# BlueBoard_v1.net
KiCad netlist of a schematic drawn in EAGLE
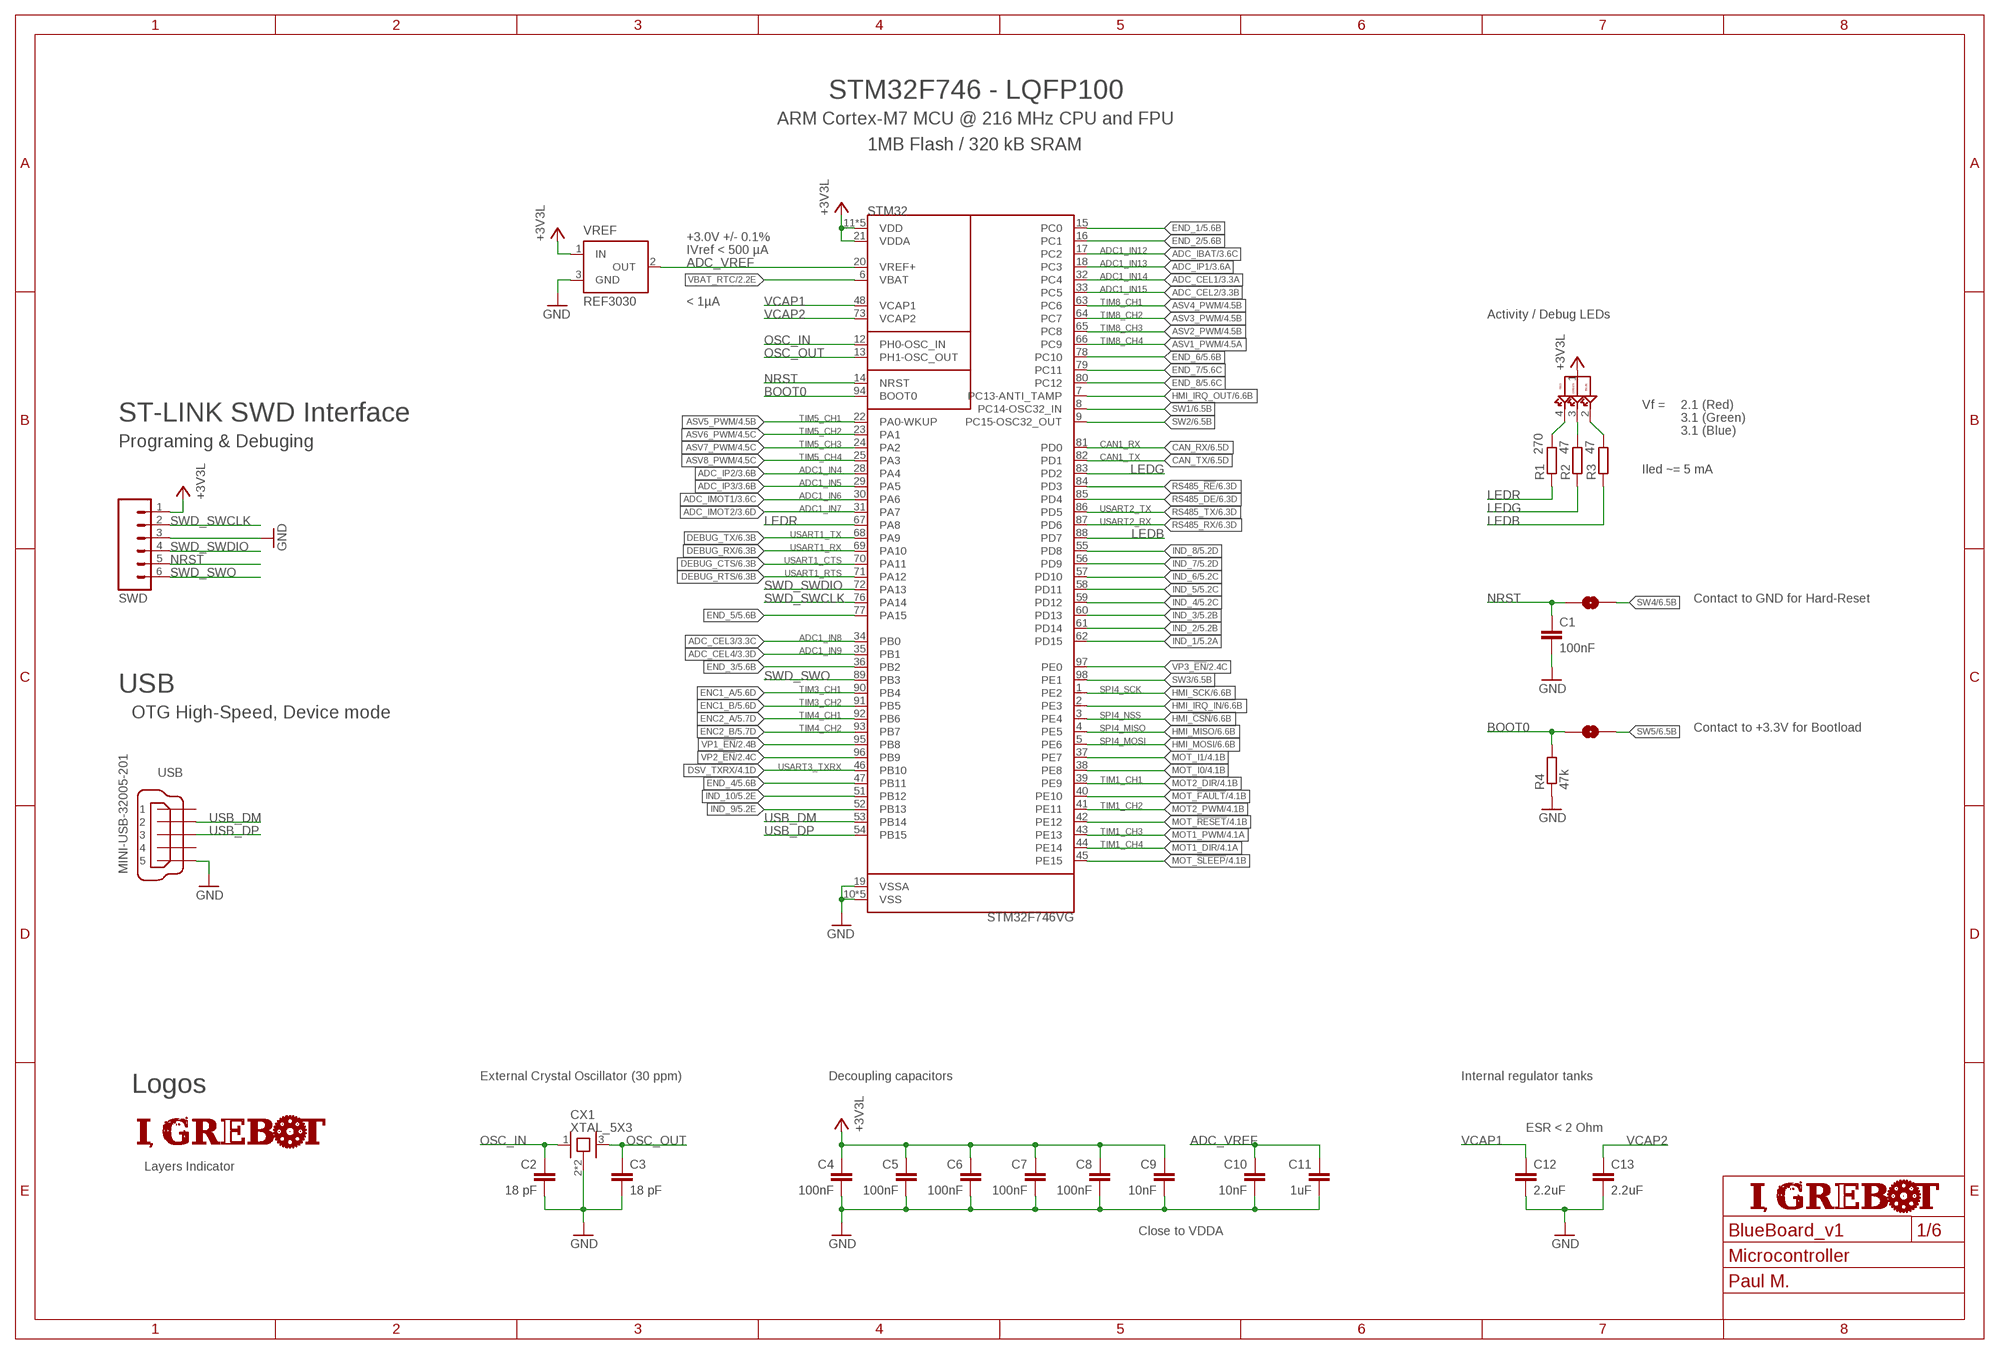
[diagram p0: schematic, sheet 1]
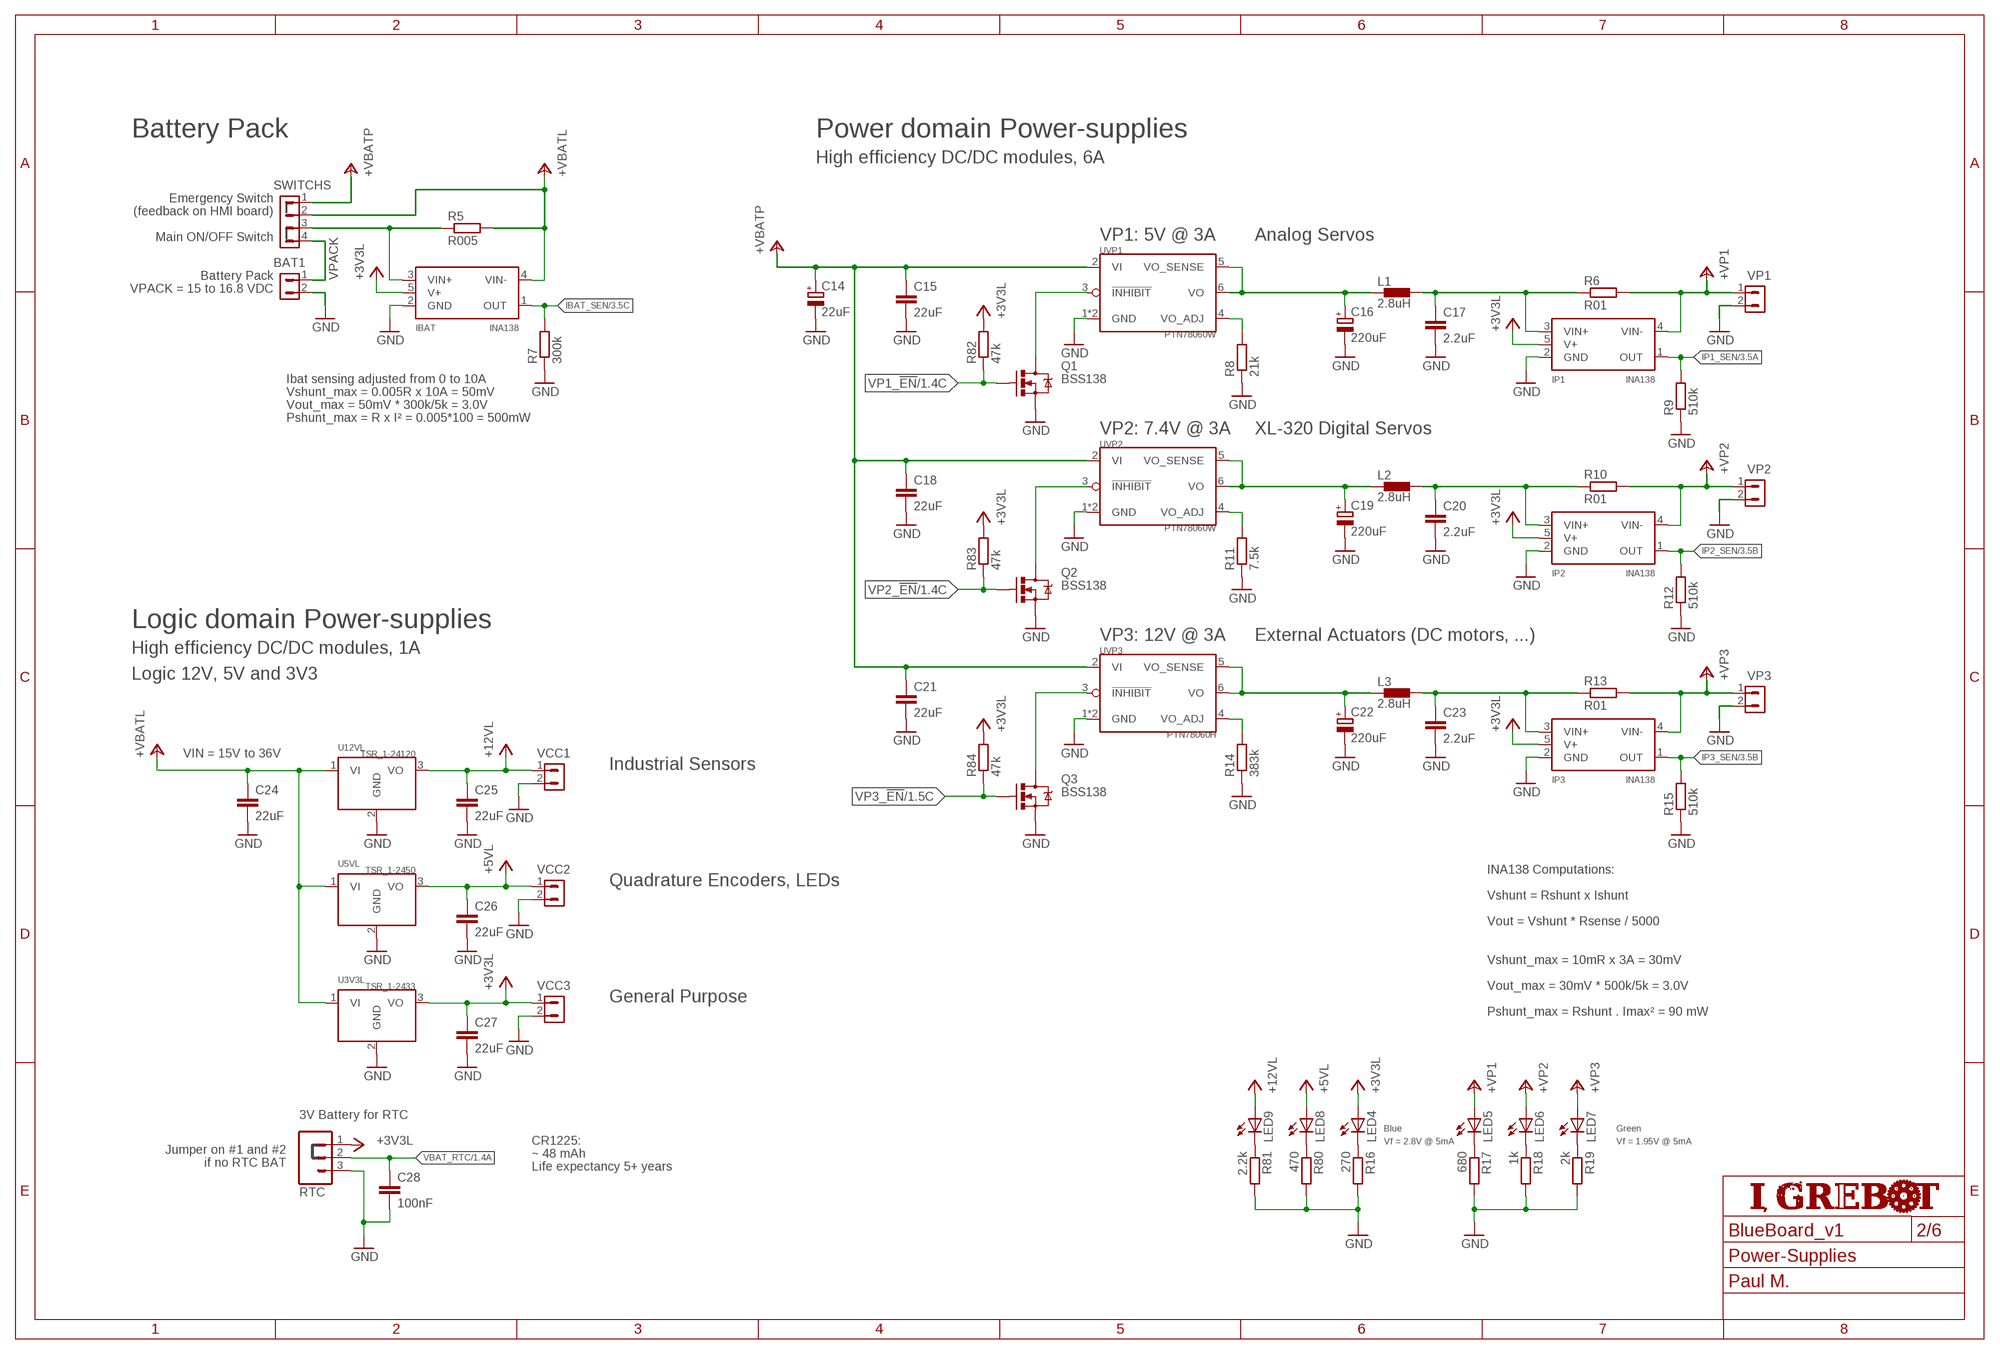
[diagram p1: schematic, sheet 2]
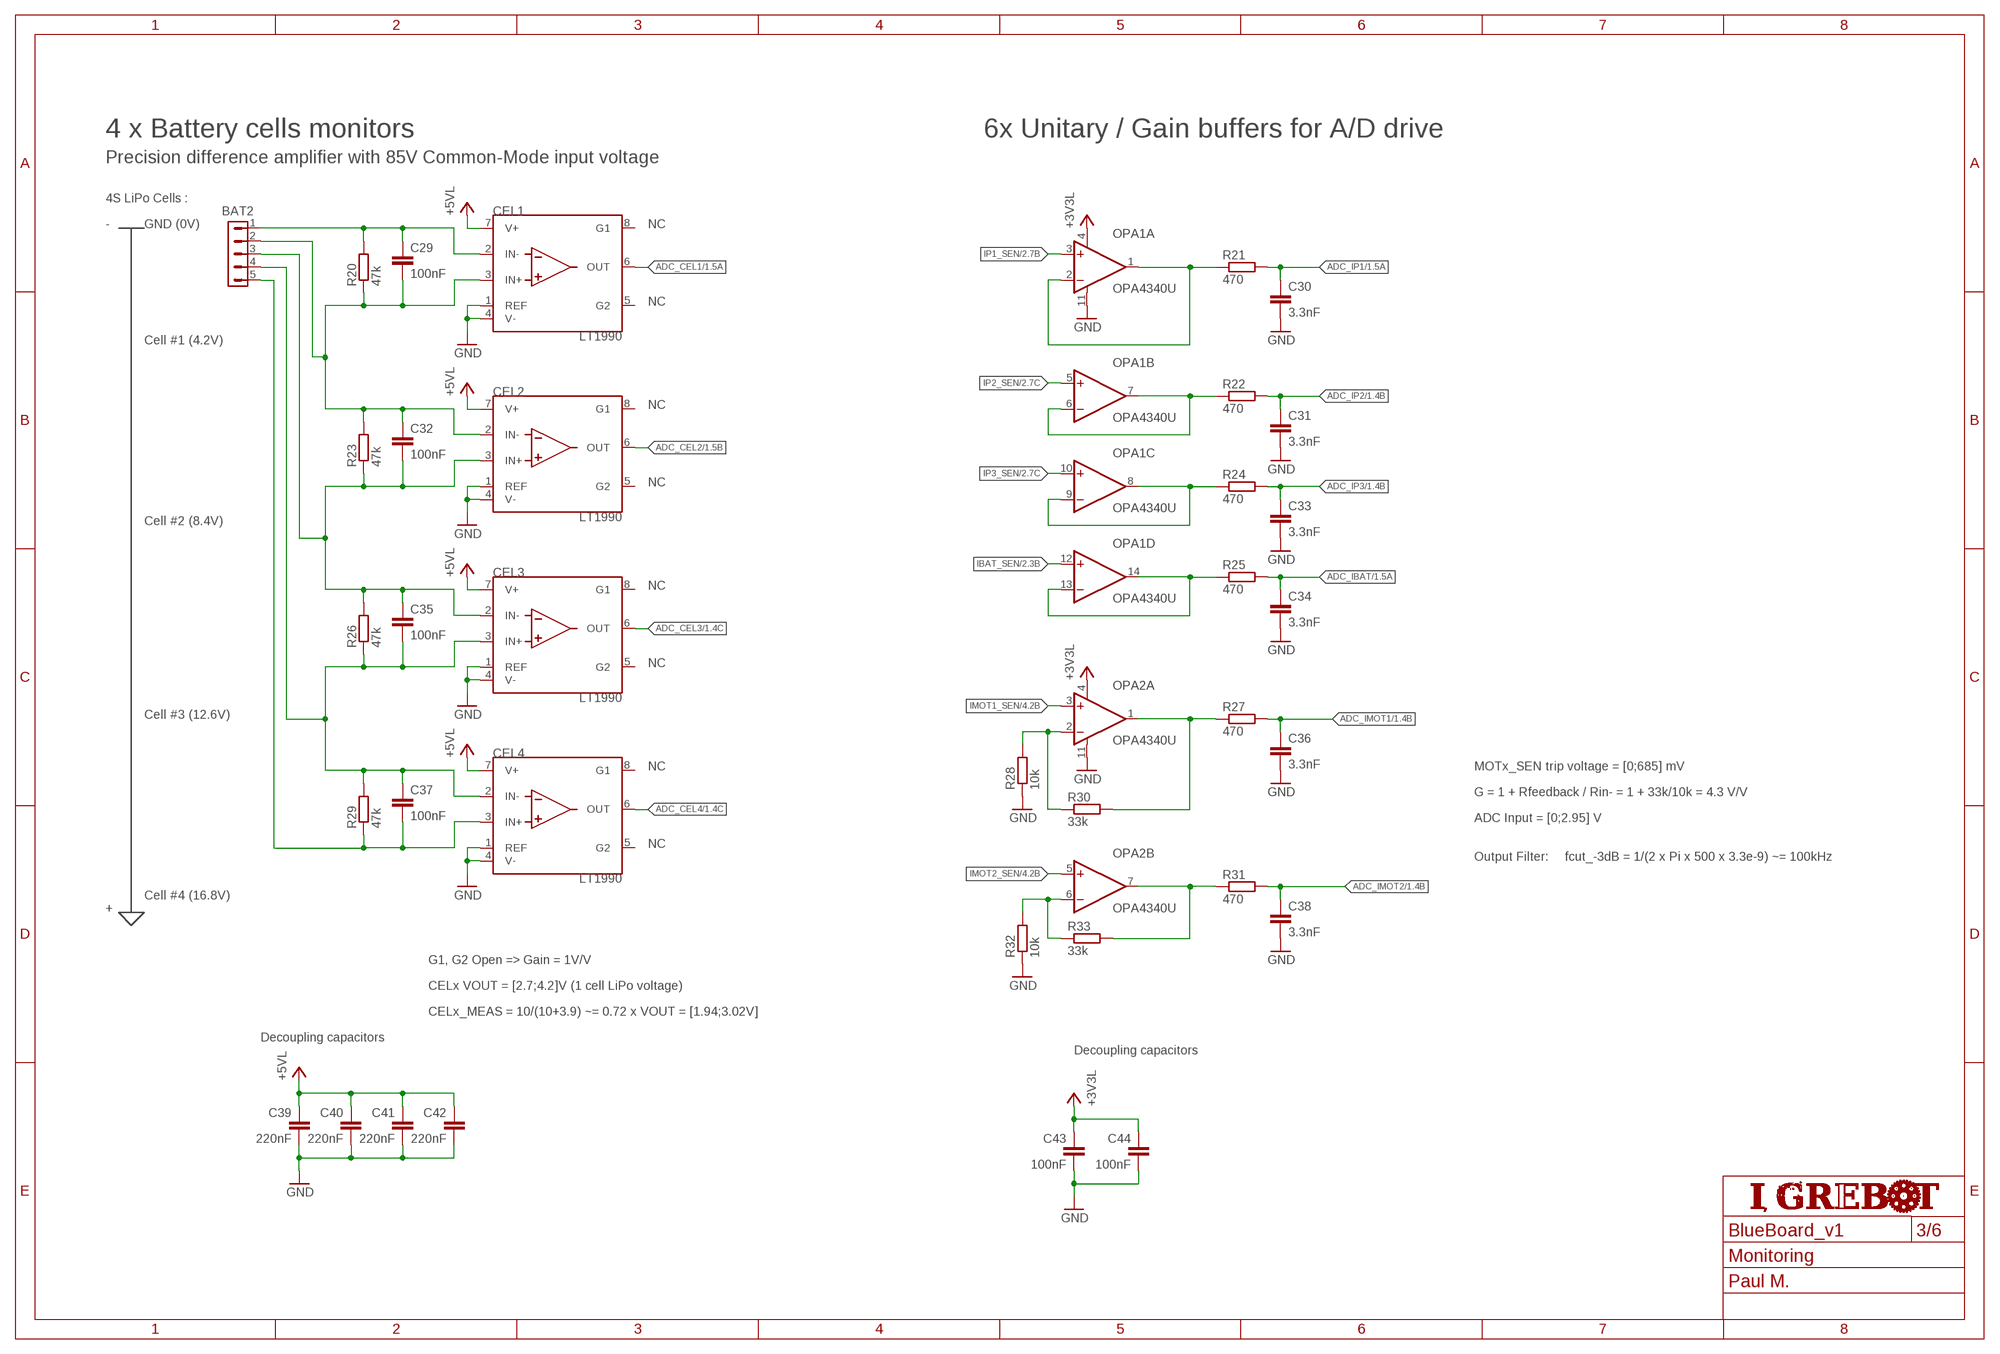
[diagram p2: schematic, sheet 3]
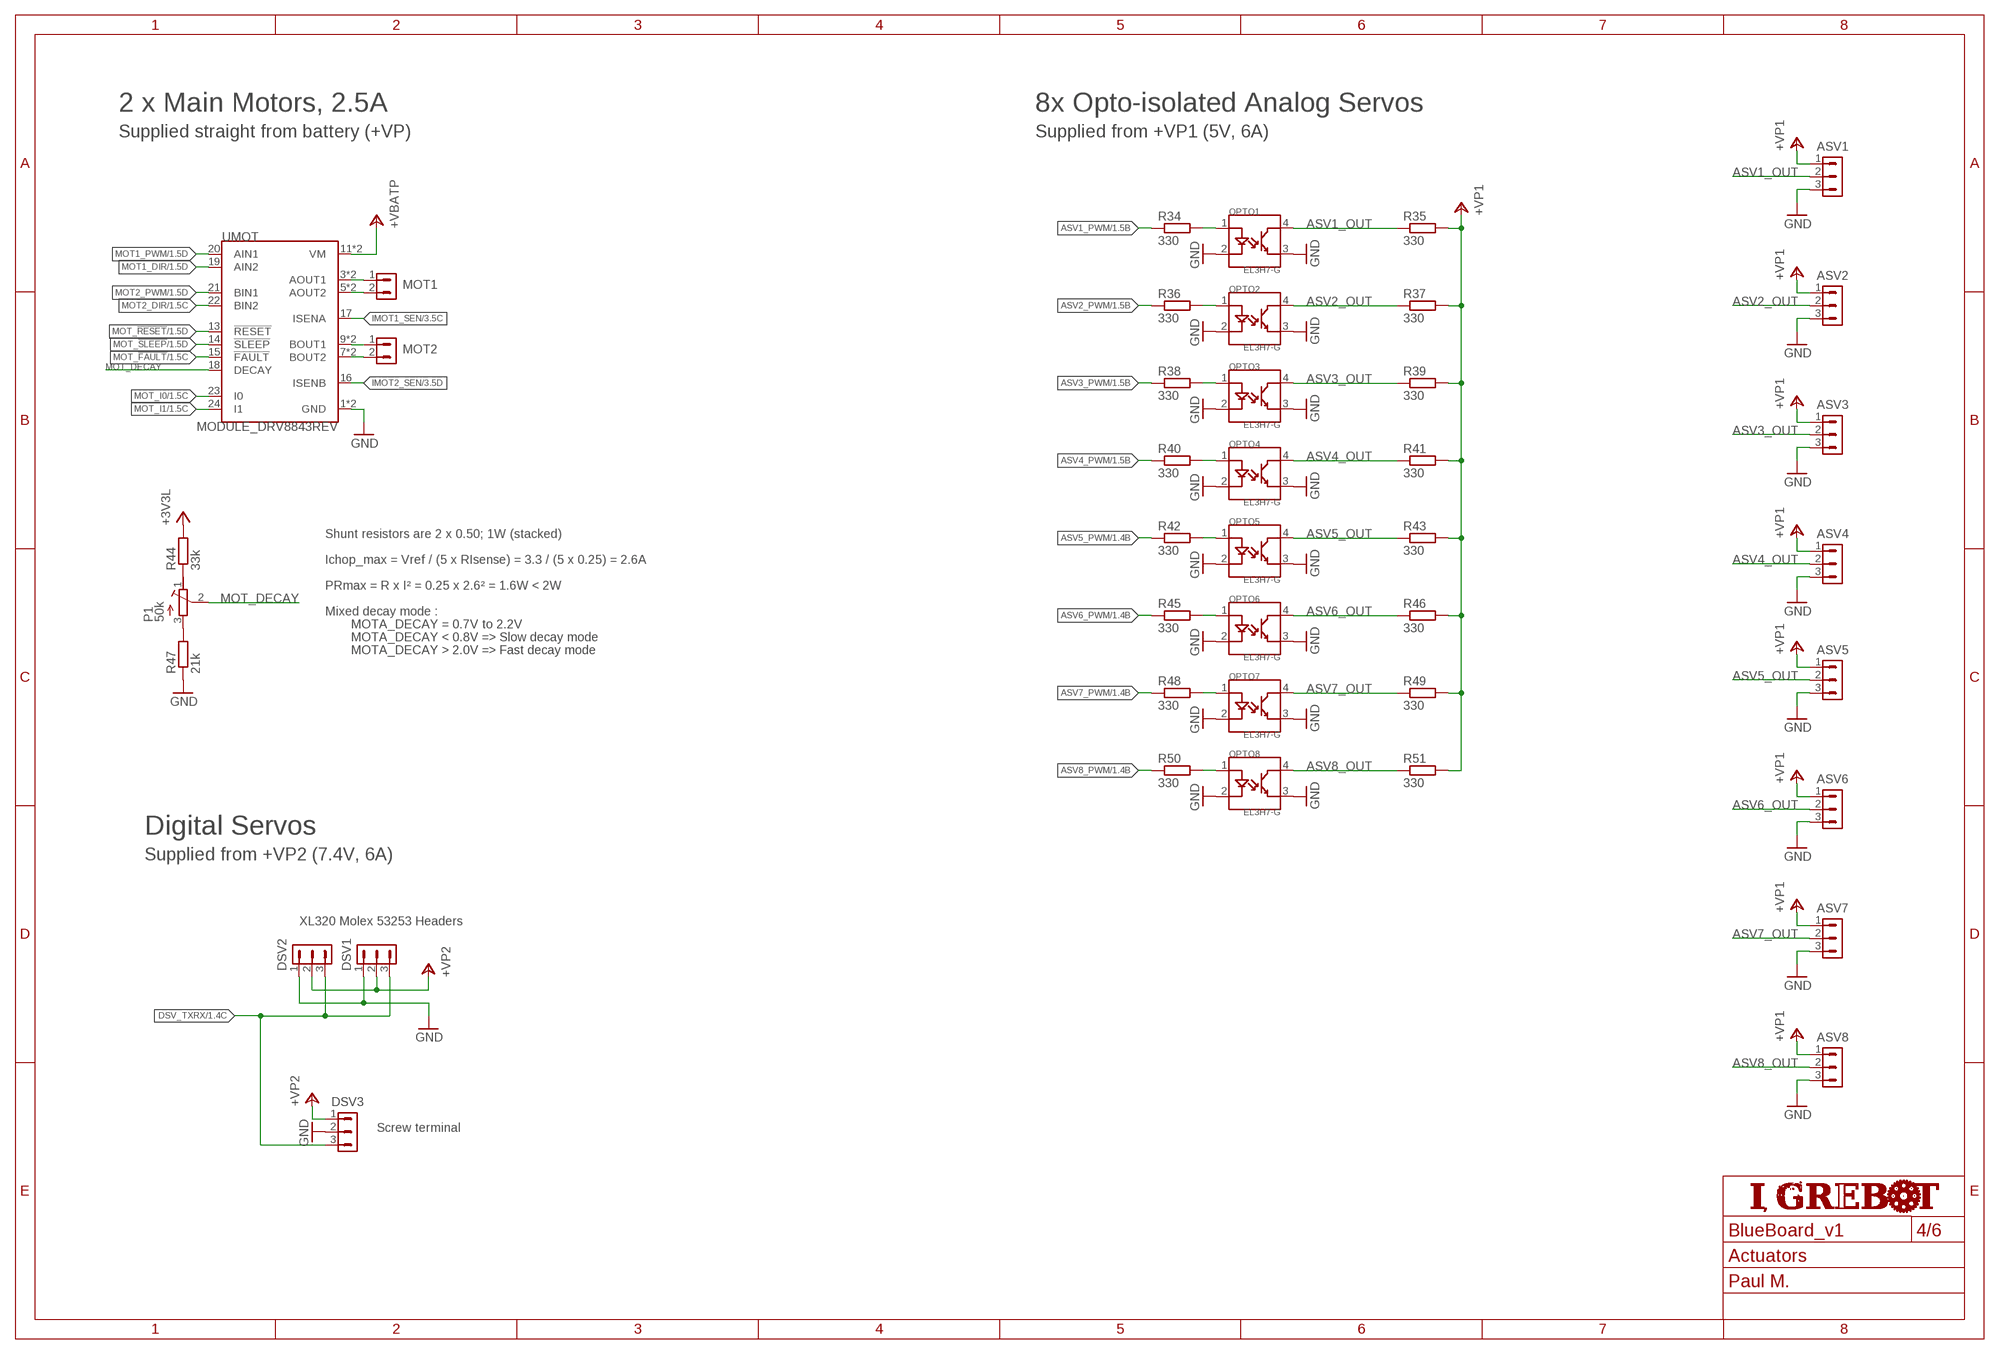
[diagram p3: schematic, sheet 4]
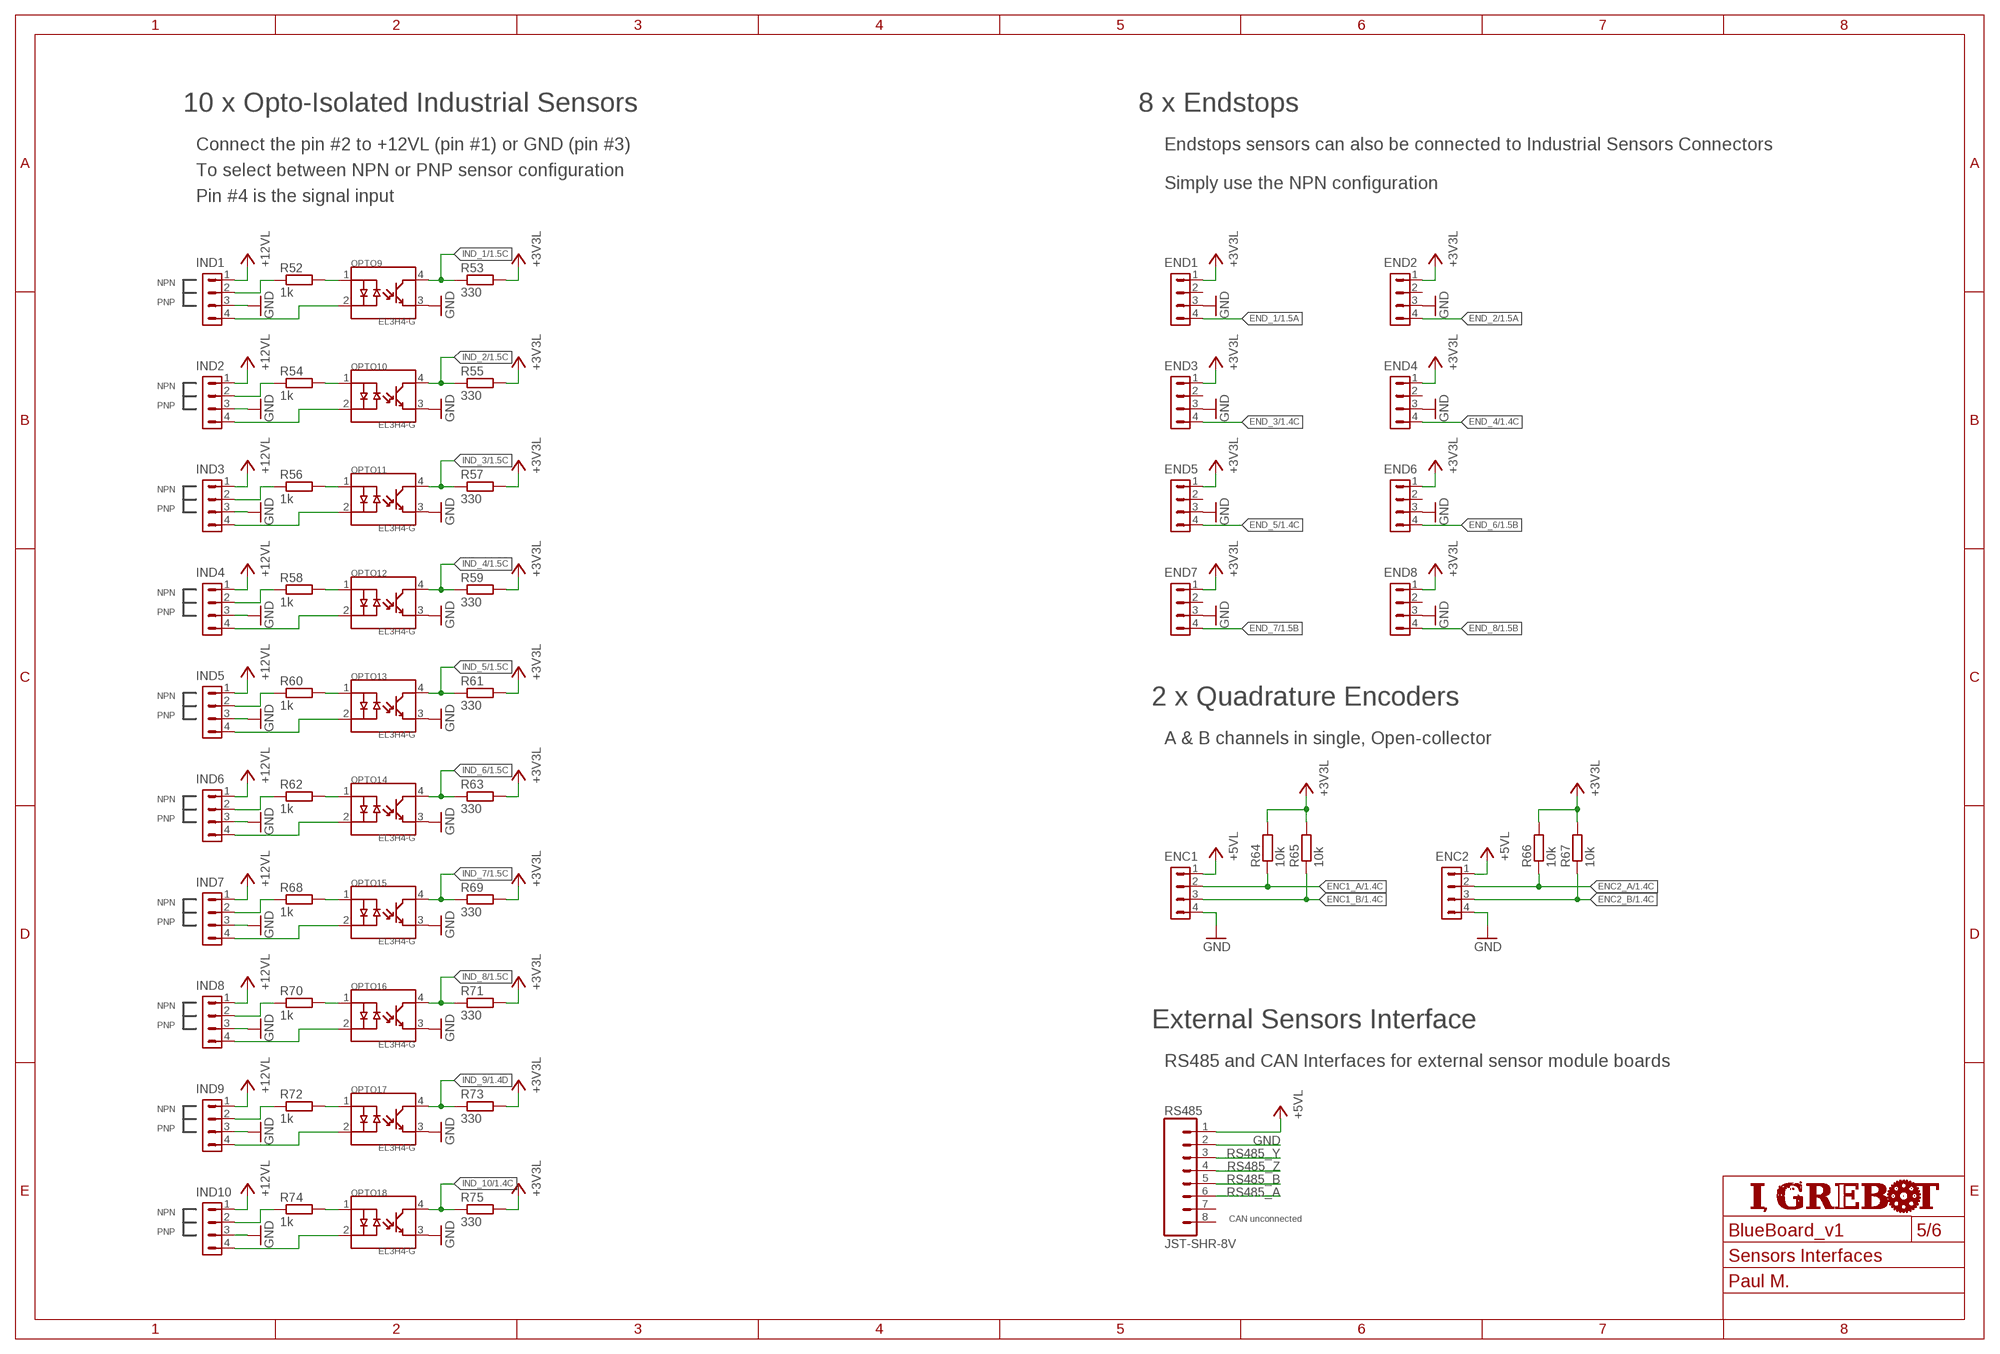
[diagram p4: schematic, sheet 5]
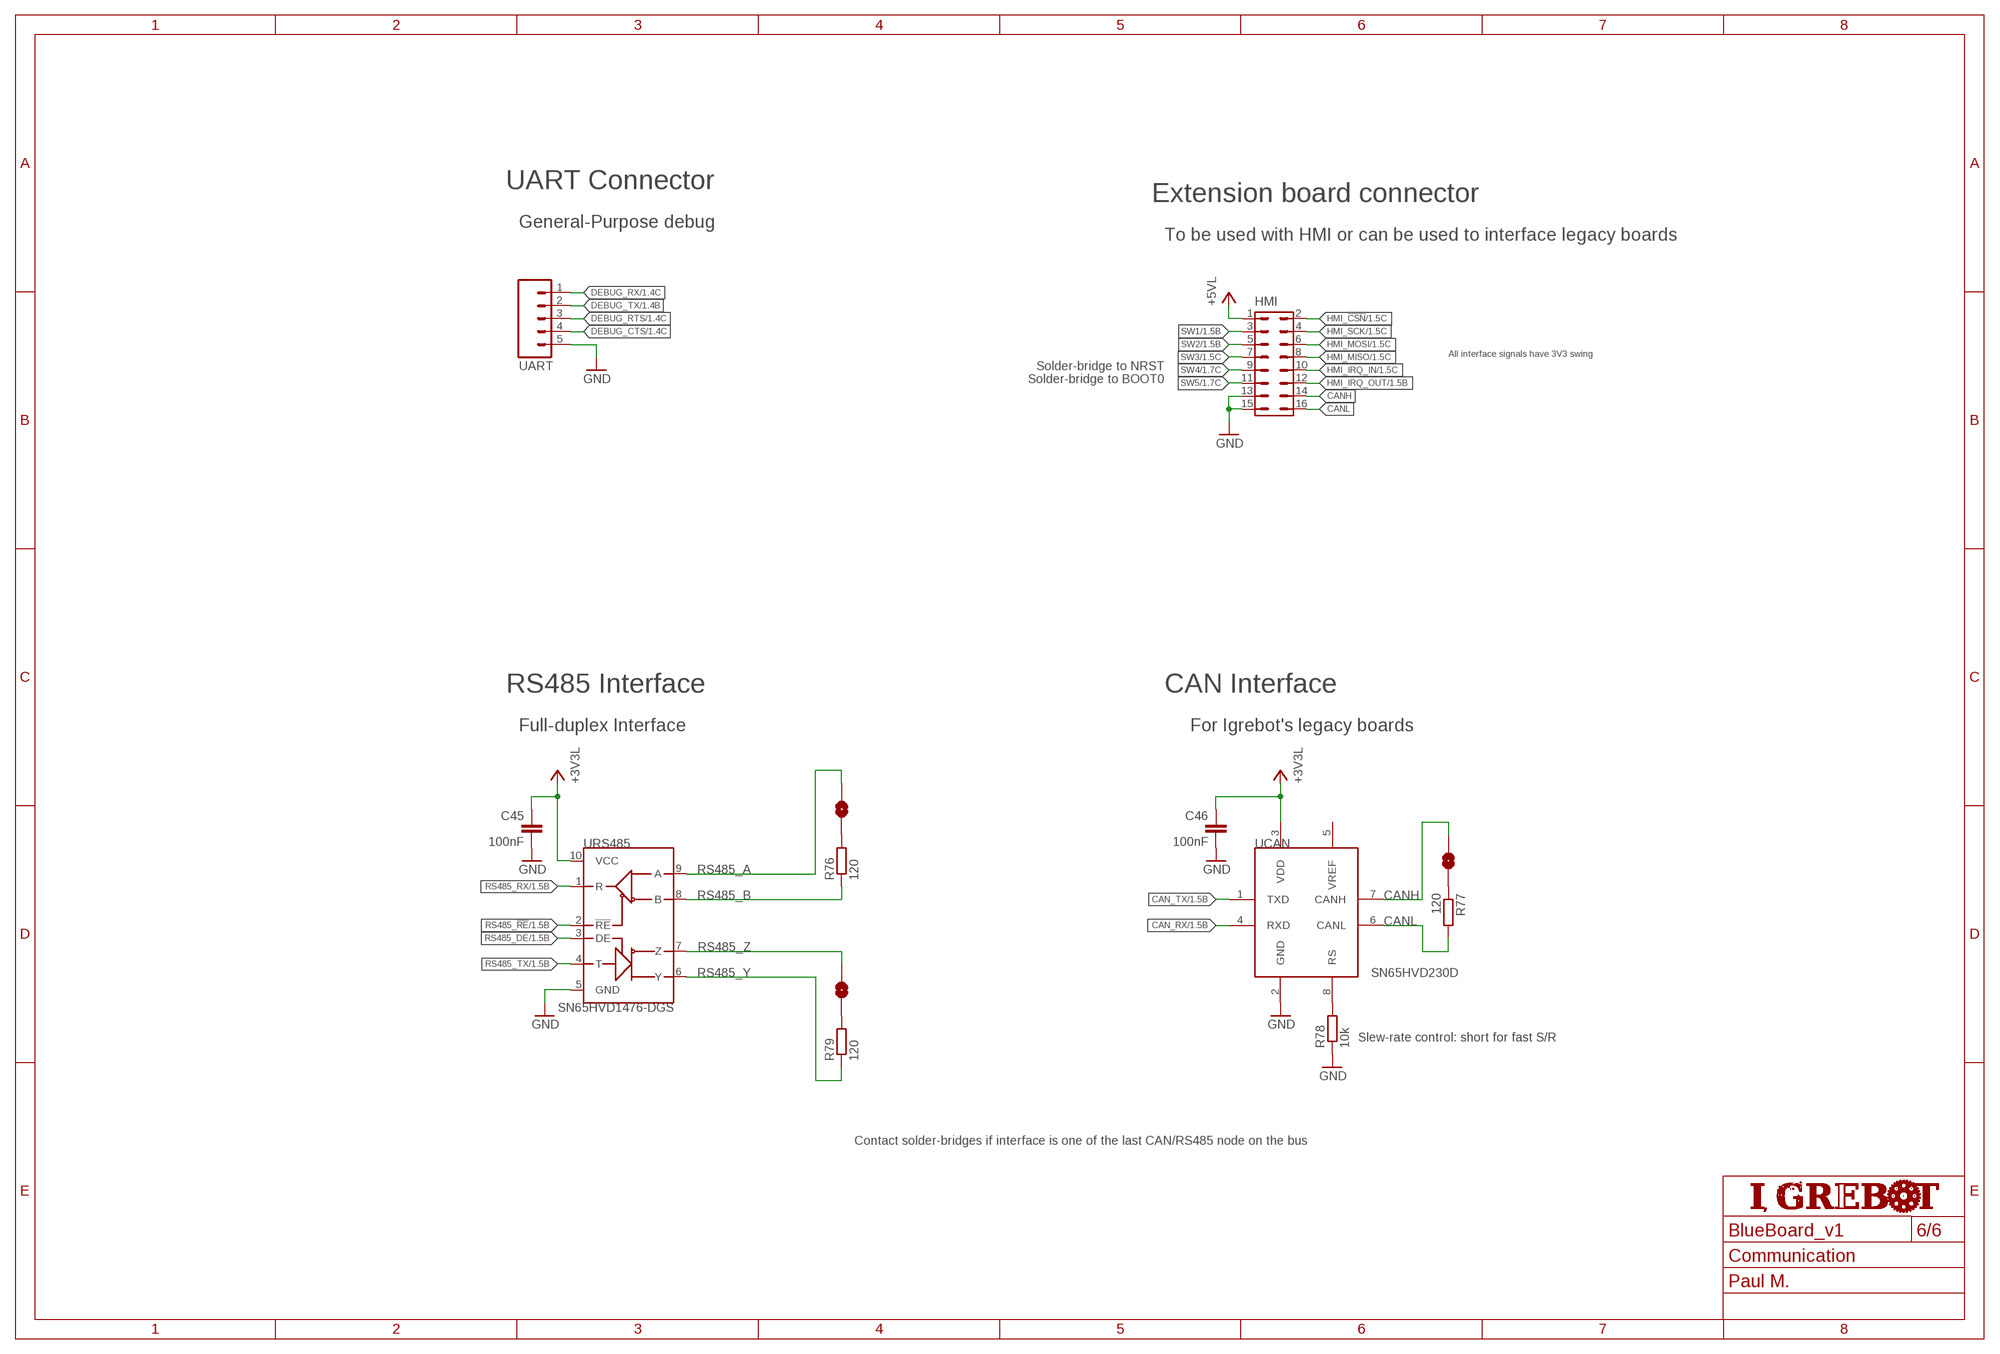
[diagram p5: schematic, sheet 6]

(export (version "E")
  (design (tool "Eeschema 10.0.6"))
  (components
    (comp (ref "BAT2")
      (value "JST-XH-S_5")
      (footprint "eagle-import:JST-XH-5S")
      (libsource (lib "eagle-import") (part "JST-XH-S_5"))
    )
    (comp (ref "C29")
      (value "100nF")
      (footprint "eagle-import:C0603")
      (libsource (lib "eagle-import") (part "C-EUC0603"))
    )
    (comp (ref "C30")
      (value "3.3nF")
      (footprint "eagle-import:C0603")
      (libsource (lib "eagle-import") (part "C-EUC0603"))
    )
    (comp (ref "C31")
      (value "3.3nF")
      (footprint "eagle-import:C0603")
      (libsource (lib "eagle-import") (part "C-EUC0603"))
    )
    (comp (ref "C32")
      (value "100nF")
      (footprint "eagle-import:C0603")
      (libsource (lib "eagle-import") (part "C-EUC0603"))
    )
    (comp (ref "C33")
      (value "3.3nF")
      (footprint "eagle-import:C0603")
      (libsource (lib "eagle-import") (part "C-EUC0603"))
    )
    (comp (ref "C34")
      (value "3.3nF")
      (footprint "eagle-import:C0603")
      (libsource (lib "eagle-import") (part "C-EUC0603"))
    )
    (comp (ref "C35")
      (value "100nF")
      (footprint "eagle-import:C0603")
      (libsource (lib "eagle-import") (part "C-EUC0603"))
    )
    (comp (ref "C36")
      (value "3.3nF")
      (footprint "eagle-import:C0603")
      (libsource (lib "eagle-import") (part "C-EUC0603"))
    )
    (comp (ref "C37")
      (value "100nF")
      (footprint "eagle-import:C0603")
      (libsource (lib "eagle-import") (part "C-EUC0603"))
    )
    (comp (ref "C38")
      (value "3.3nF")
      (footprint "eagle-import:C0603")
      (libsource (lib "eagle-import") (part "C-EUC0603"))
    )
    (comp (ref "C39")
      (value "220nF")
      (footprint "eagle-import:C0603")
      (libsource (lib "eagle-import") (part "C-EUC0603"))
    )
    (comp (ref "C40")
      (value "220nF")
      (footprint "eagle-import:C0603")
      (libsource (lib "eagle-import") (part "C-EUC0603"))
    )
    (comp (ref "C41")
      (value "220nF")
      (footprint "eagle-import:C0603")
      (libsource (lib "eagle-import") (part "C-EUC0603"))
    )
    (comp (ref "C42")
      (value "220nF")
      (footprint "eagle-import:C0603")
      (libsource (lib "eagle-import") (part "C-EUC0603"))
    )
    (comp (ref "C43")
      (value "100nF")
      (footprint "eagle-import:C0603")
      (libsource (lib "eagle-import") (part "C-EUC0603"))
    )
    (comp (ref "C44")
      (value "100nF")
      (footprint "eagle-import:C0603")
      (libsource (lib "eagle-import") (part "C-EUC0603"))
    )
    (comp (ref "CEL1")
      (value "LT1990")
      (footprint "eagle-import:S8")
      (libsource (lib "eagle-import") (part "LT1990"))
    )
    (comp (ref "CEL2")
      (value "LT1990")
      (footprint "eagle-import:S8")
      (libsource (lib "eagle-import") (part "LT1990"))
    )
    (comp (ref "CEL3")
      (value "LT1990")
      (footprint "eagle-import:S8")
      (libsource (lib "eagle-import") (part "LT1990"))
    )
    (comp (ref "CEL4")
      (value "LT1990")
      (footprint "eagle-import:S8")
      (libsource (lib "eagle-import") (part "LT1990"))
    )
    (comp (ref "OPA1")
      (value "OPA4340U")
      (footprint "eagle-import:SO14")
      (fields (field (name "MF") "TEXAS INSTRUMENTS") (field (name "MPN") "OPA4340UA"))
      (libsource (lib "eagle-import") (part "OPA4340U"))
    )
    (comp (ref "OPA2")
      (value "OPA4340U")
      (footprint "eagle-import:SO14")
      (fields (field (name "MF") "TEXAS INSTRUMENTS") (field (name "MPN") "OPA4340UA"))
      (libsource (lib "eagle-import") (part "OPA4340U"))
    )
    (comp (ref "R20")
      (value "47k")
      (footprint "eagle-import:R0603")
      (libsource (lib "eagle-import") (part "resistor_R-EU_R0603"))
    )
    (comp (ref "R21")
      (value "470")
      (footprint "eagle-import:R0603")
      (libsource (lib "eagle-import") (part "R-EU_R0603"))
    )
    (comp (ref "R22")
      (value "470")
      (footprint "eagle-import:R0603")
      (libsource (lib "eagle-import") (part "R-EU_R0603"))
    )
    (comp (ref "R23")
      (value "47k")
      (footprint "eagle-import:R0603")
      (libsource (lib "eagle-import") (part "resistor_R-EU_R0603"))
    )
    (comp (ref "R24")
      (value "470")
      (footprint "eagle-import:R0603")
      (libsource (lib "eagle-import") (part "R-EU_R0603"))
    )
    (comp (ref "R25")
      (value "470")
      (footprint "eagle-import:R0603")
      (libsource (lib "eagle-import") (part "R-EU_R0603"))
    )
    (comp (ref "R26")
      (value "47k")
      (footprint "eagle-import:R0603")
      (libsource (lib "eagle-import") (part "resistor_R-EU_R0603"))
    )
    (comp (ref "R27")
      (value "470")
      (footprint "eagle-import:R0603")
      (libsource (lib "eagle-import") (part "R-EU_R0603"))
    )
    (comp (ref "R28")
      (value "10k")
      (footprint "eagle-import:R0603")
      (libsource (lib "eagle-import") (part "R-EU_R0603"))
    )
    (comp (ref "R29")
      (value "47k")
      (footprint "eagle-import:R0603")
      (libsource (lib "eagle-import") (part "resistor_R-EU_R0603"))
    )
    (comp (ref "R30")
      (value "33k")
      (footprint "eagle-import:R0603")
      (libsource (lib "eagle-import") (part "R-EU_R0603"))
    )
    (comp (ref "R31")
      (value "470")
      (footprint "eagle-import:R0603")
      (libsource (lib "eagle-import") (part "R-EU_R0603"))
    )
    (comp (ref "R32")
      (value "10k")
      (footprint "eagle-import:R0603")
      (libsource (lib "eagle-import") (part "R-EU_R0603"))
    )
    (comp (ref "R33")
      (value "33k")
      (footprint "eagle-import:R0603")
      (libsource (lib "eagle-import") (part "R-EU_R0603"))
    )
    (comp (ref "ASV1")
      (value "CON_3.5_3")
      (footprint "eagle-import:CON_3.5_3")
      (libsource (lib "eagle-import") (part "CON_3.5_3"))
    )
    (comp (ref "ASV2")
      (value "CON_3.5_3")
      (footprint "eagle-import:CON_3.5_3")
      (libsource (lib "eagle-import") (part "CON_3.5_3"))
    )
    (comp (ref "ASV3")
      (value "CON_3.5_3")
      (footprint "eagle-import:CON_3.5_3")
      (libsource (lib "eagle-import") (part "CON_3.5_3"))
    )
    (comp (ref "ASV4")
      (value "CON_3.5_3")
      (footprint "eagle-import:CON_3.5_3")
      (libsource (lib "eagle-import") (part "CON_3.5_3"))
    )
    (comp (ref "ASV5")
      (value "CON_3.5_3")
      (footprint "eagle-import:CON_3.5_3")
      (libsource (lib "eagle-import") (part "CON_3.5_3"))
    )
    (comp (ref "ASV6")
      (value "CON_3.5_3")
      (footprint "eagle-import:CON_3.5_3")
      (libsource (lib "eagle-import") (part "CON_3.5_3"))
    )
    (comp (ref "ASV7")
      (value "CON_3.5_3")
      (footprint "eagle-import:CON_3.5_3")
      (libsource (lib "eagle-import") (part "CON_3.5_3"))
    )
    (comp (ref "ASV8")
      (value "CON_3.5_3")
      (footprint "eagle-import:CON_3.5_3")
      (libsource (lib "eagle-import") (part "CON_3.5_3"))
    )
    (comp (ref "DSV1")
      (value "CON_2.00_MOLEX-53253_3")
      (footprint "eagle-import:CON_2.00_MOLEX-53253_3")
      (libsource (lib "eagle-import") (part "CON_2.00_MOLEX-53253_3"))
    )
    (comp (ref "DSV2")
      (value "CON_2.00_MOLEX-53253_3")
      (footprint "eagle-import:CON_2.00_MOLEX-53253_3")
      (libsource (lib "eagle-import") (part "CON_2.00_MOLEX-53253_3"))
    )
    (comp (ref "DSV3")
      (value "CON_3.5_3")
      (footprint "eagle-import:CON_3.5_3")
      (libsource (lib "eagle-import") (part "CON_3.5_3"))
    )
    (comp (ref "MOT1")
      (value "CON_3.5_2")
      (footprint "eagle-import:CON_3.5_2")
      (libsource (lib "eagle-import") (part "CON_3.5_2"))
    )
    (comp (ref "MOT2")
      (value "CON_3.5_2")
      (footprint "eagle-import:CON_3.5_2")
      (libsource (lib "eagle-import") (part "CON_3.5_2"))
    )
    (comp (ref "OPTO1")
      (value "EL3H7-G")
      (footprint "eagle-import:SSOP_4")
      (libsource (lib "eagle-import") (part "EL3H7-G"))
    )
    (comp (ref "OPTO2")
      (value "EL3H7-G")
      (footprint "eagle-import:SSOP_4")
      (libsource (lib "eagle-import") (part "EL3H7-G"))
    )
    (comp (ref "OPTO3")
      (value "EL3H7-G")
      (footprint "eagle-import:SSOP_4")
      (libsource (lib "eagle-import") (part "EL3H7-G"))
    )
    (comp (ref "OPTO4")
      (value "EL3H7-G")
      (footprint "eagle-import:SSOP_4")
      (libsource (lib "eagle-import") (part "EL3H7-G"))
    )
    (comp (ref "OPTO5")
      (value "EL3H7-G")
      (footprint "eagle-import:SSOP_4")
      (libsource (lib "eagle-import") (part "EL3H7-G"))
    )
    (comp (ref "OPTO6")
      (value "EL3H7-G")
      (footprint "eagle-import:SSOP_4")
      (libsource (lib "eagle-import") (part "EL3H7-G"))
    )
    (comp (ref "OPTO7")
      (value "EL3H7-G")
      (footprint "eagle-import:SSOP_4")
      (libsource (lib "eagle-import") (part "EL3H7-G"))
    )
    (comp (ref "OPTO8")
      (value "EL3H7-G")
      (footprint "eagle-import:SSOP_4")
      (libsource (lib "eagle-import") (part "EL3H7-G"))
    )
    (comp (ref "P1")
      (value "50k")
      (footprint "eagle-import:RTRIMT93XB")
      (libsource (lib "eagle-import") (part "R-TRIMMT93XB"))
    )
    (comp (ref "R34")
      (value "330")
      (footprint "eagle-import:R0603")
      (libsource (lib "eagle-import") (part "resistor_R-EU_R0603"))
    )
    (comp (ref "R35")
      (value "330")
      (footprint "eagle-import:R0603")
      (libsource (lib "eagle-import") (part "resistor_R-EU_R0603"))
    )
    (comp (ref "R36")
      (value "330")
      (footprint "eagle-import:R0603")
      (libsource (lib "eagle-import") (part "resistor_R-EU_R0603"))
    )
    (comp (ref "R37")
      (value "330")
      (footprint "eagle-import:R0603")
      (libsource (lib "eagle-import") (part "resistor_R-EU_R0603"))
    )
    (comp (ref "R38")
      (value "330")
      (footprint "eagle-import:R0603")
      (libsource (lib "eagle-import") (part "resistor_R-EU_R0603"))
    )
    (comp (ref "R39")
      (value "330")
      (footprint "eagle-import:R0603")
      (libsource (lib "eagle-import") (part "resistor_R-EU_R0603"))
    )
    (comp (ref "R40")
      (value "330")
      (footprint "eagle-import:R0603")
      (libsource (lib "eagle-import") (part "resistor_R-EU_R0603"))
    )
    (comp (ref "R41")
      (value "330")
      (footprint "eagle-import:R0603")
      (libsource (lib "eagle-import") (part "resistor_R-EU_R0603"))
    )
    (comp (ref "R42")
      (value "330")
      (footprint "eagle-import:R0603")
      (libsource (lib "eagle-import") (part "resistor_R-EU_R0603"))
    )
    (comp (ref "R43")
      (value "330")
      (footprint "eagle-import:R0603")
      (libsource (lib "eagle-import") (part "resistor_R-EU_R0603"))
    )
    (comp (ref "R44")
      (value "33k")
      (footprint "eagle-import:R0603")
      (libsource (lib "eagle-import") (part "resistor_R-EU_R0603"))
    )
    (comp (ref "R45")
      (value "330")
      (footprint "eagle-import:R0603")
      (libsource (lib "eagle-import") (part "resistor_R-EU_R0603"))
    )
    (comp (ref "R46")
      (value "330")
      (footprint "eagle-import:R0603")
      (libsource (lib "eagle-import") (part "resistor_R-EU_R0603"))
    )
    (comp (ref "R47")
      (value "21k")
      (footprint "eagle-import:R0603")
      (libsource (lib "eagle-import") (part "resistor_R-EU_R0603"))
    )
    (comp (ref "R48")
      (value "330")
      (footprint "eagle-import:R0603")
      (libsource (lib "eagle-import") (part "resistor_R-EU_R0603"))
    )
    (comp (ref "R49")
      (value "330")
      (footprint "eagle-import:R0603")
      (libsource (lib "eagle-import") (part "resistor_R-EU_R0603"))
    )
    (comp (ref "R50")
      (value "330")
      (footprint "eagle-import:R0603")
      (libsource (lib "eagle-import") (part "resistor_R-EU_R0603"))
    )
    (comp (ref "R51")
      (value "330")
      (footprint "eagle-import:R0603")
      (libsource (lib "eagle-import") (part "resistor_R-EU_R0603"))
    )
    (comp (ref "UMOT")
      (value "MODULE_DRV8843REV")
      (footprint "eagle-import:MODULE_DRV884X_REV")
      (libsource (lib "eagle-import") (part "MODULE_DRV8843REV"))
    )
    (comp (ref "BAT1")
      (value "MC15-GF-3.81-LR_2")
      (footprint "eagle-import:CON_3.81_LR_2")
      (libsource (lib "eagle-import") (part "MC15-GF-3.81-LR_2"))
    )
    (comp (ref "C14")
      (value "22uF")
      (footprint "eagle-import:PANASONIC_B")
      (libsource (lib "eagle-import") (part "CPOL-EUB"))
    )
    (comp (ref "C15")
      (value "22uF")
      (footprint "eagle-import:C3225")
      (libsource (lib "eagle-import") (part "C-EUC3225"))
    )
    (comp (ref "C16")
      (value "220uF")
      (footprint "eagle-import:PANASONIC_D")
      (libsource (lib "eagle-import") (part "CPOL-EUD"))
    )
    (comp (ref "C17")
      (value "2.2uF")
      (footprint "eagle-import:C3225")
      (libsource (lib "eagle-import") (part "C-EUC3225"))
    )
    (comp (ref "C18")
      (value "22uF")
      (footprint "eagle-import:C3225")
      (libsource (lib "eagle-import") (part "C-EUC3225"))
    )
    (comp (ref "C19")
      (value "220uF")
      (footprint "eagle-import:PANASONIC_D")
      (libsource (lib "eagle-import") (part "CPOL-EUD"))
    )
    (comp (ref "C20")
      (value "2.2uF")
      (footprint "eagle-import:C3225")
      (libsource (lib "eagle-import") (part "C-EUC3225"))
    )
    (comp (ref "C21")
      (value "22uF")
      (footprint "eagle-import:C3225")
      (libsource (lib "eagle-import") (part "C-EUC3225"))
    )
    (comp (ref "C22")
      (value "220uF")
      (footprint "eagle-import:PANASONIC_D")
      (libsource (lib "eagle-import") (part "CPOL-EUD"))
    )
    (comp (ref "C23")
      (value "2.2uF")
      (footprint "eagle-import:C3225")
      (libsource (lib "eagle-import") (part "C-EUC3225"))
    )
    (comp (ref "C24")
      (value "22uF")
      (footprint "eagle-import:C3225")
      (libsource (lib "eagle-import") (part "C-EUC3225"))
    )
    (comp (ref "C25")
      (value "22uF")
      (footprint "eagle-import:C1210")
      (libsource (lib "eagle-import") (part "C-EUC1210"))
    )
    (comp (ref "C26")
      (value "22uF")
      (footprint "eagle-import:C1210")
      (libsource (lib "eagle-import") (part "C-EUC1210"))
    )
    (comp (ref "C27")
      (value "22uF")
      (footprint "eagle-import:C1210")
      (libsource (lib "eagle-import") (part "C-EUC1210"))
    )
    (comp (ref "C28")
      (value "100nF")
      (footprint "eagle-import:C0603")
      (libsource (lib "eagle-import") (part "C-EUC0603"))
    )
    (comp (ref "IBAT")
      (value "INA138")
      (footprint "eagle-import:DBV_05")
      (libsource (lib "eagle-import") (part "INA138"))
    )
    (comp (ref "IP1")
      (value "INA138")
      (footprint "eagle-import:DBV_05")
      (libsource (lib "eagle-import") (part "INA138"))
    )
    (comp (ref "IP2")
      (value "INA138")
      (footprint "eagle-import:DBV_05")
      (libsource (lib "eagle-import") (part "INA138"))
    )
    (comp (ref "IP3")
      (value "INA138")
      (footprint "eagle-import:DBV_05")
      (libsource (lib "eagle-import") (part "INA138"))
    )
    (comp (ref "L1")
      (value "2.8uH")
      (footprint "eagle-import:DR1030")
      (libsource (lib "eagle-import") (part "DR1030"))
    )
    (comp (ref "L2")
      (value "2.8uH")
      (footprint "eagle-import:DR1030")
      (libsource (lib "eagle-import") (part "DR1030"))
    )
    (comp (ref "L3")
      (value "2.8uH")
      (footprint "eagle-import:DR1030")
      (libsource (lib "eagle-import") (part "DR1030"))
    )
    (comp (ref "LED4")
      (value "LEDCHIP-LED0805")
      (footprint "eagle-import:CHIP-LED0805")
      (libsource (lib "eagle-import") (part "LEDCHIP-LED0805"))
    )
    (comp (ref "LED5")
      (value "LEDCHIP-LED0805")
      (footprint "eagle-import:CHIP-LED0805")
      (libsource (lib "eagle-import") (part "LEDCHIP-LED0805"))
    )
    (comp (ref "LED6")
      (value "LEDCHIP-LED0805")
      (footprint "eagle-import:CHIP-LED0805")
      (libsource (lib "eagle-import") (part "LEDCHIP-LED0805"))
    )
    (comp (ref "LED7")
      (value "LEDCHIP-LED0805")
      (footprint "eagle-import:CHIP-LED0805")
      (libsource (lib "eagle-import") (part "LEDCHIP-LED0805"))
    )
    (comp (ref "LED8")
      (value "LEDCHIP-LED0805")
      (footprint "eagle-import:CHIP-LED0805")
      (libsource (lib "eagle-import") (part "LEDCHIP-LED0805"))
    )
    (comp (ref "LED9")
      (value "LEDCHIP-LED0805")
      (footprint "eagle-import:CHIP-LED0805")
      (libsource (lib "eagle-import") (part "LEDCHIP-LED0805"))
    )
    (comp (ref "Q1")
      (value "BSS138")
      (footprint "eagle-import:SOT23")
      (libsource (lib "eagle-import") (part "MOSFET-NCHANNELBSS138"))
    )
    (comp (ref "Q2")
      (value "BSS138")
      (footprint "eagle-import:SOT23")
      (libsource (lib "eagle-import") (part "MOSFET-NCHANNELBSS138"))
    )
    (comp (ref "Q3")
      (value "BSS138")
      (footprint "eagle-import:SOT23")
      (libsource (lib "eagle-import") (part "MOSFET-NCHANNELBSS138"))
    )
    (comp (ref "R5")
      (value "R005")
      (footprint "eagle-import:R2512")
      (libsource (lib "eagle-import") (part "R-EU_R2512"))
    )
    (comp (ref "R6")
      (value "R01")
      (footprint "eagle-import:R2512")
      (libsource (lib "eagle-import") (part "R-EU_R2512"))
    )
    (comp (ref "R7")
      (value "300k")
      (footprint "eagle-import:R0603")
      (libsource (lib "eagle-import") (part "R-EU_R0603"))
    )
    (comp (ref "R8")
      (value "21k")
      (footprint "eagle-import:R0603")
      (libsource (lib "eagle-import") (part "R-EU_R0603"))
    )
    (comp (ref "R9")
      (value "510k")
      (footprint "eagle-import:R0603")
      (libsource (lib "eagle-import") (part "R-EU_R0603"))
    )
    (comp (ref "R10")
      (value "R01")
      (footprint "eagle-import:R2512")
      (libsource (lib "eagle-import") (part "R-EU_R2512"))
    )
    (comp (ref "R11")
      (value "7.5k")
      (footprint "eagle-import:R0603")
      (libsource (lib "eagle-import") (part "R-EU_R0603"))
    )
    (comp (ref "R12")
      (value "510k")
      (footprint "eagle-import:R0603")
      (libsource (lib "eagle-import") (part "R-EU_R0603"))
    )
    (comp (ref "R13")
      (value "R01")
      (footprint "eagle-import:R2512")
      (libsource (lib "eagle-import") (part "R-EU_R2512"))
    )
    (comp (ref "R14")
      (value "383k")
      (footprint "eagle-import:R0603")
      (libsource (lib "eagle-import") (part "R-EU_R0603"))
    )
    (comp (ref "R15")
      (value "510k")
      (footprint "eagle-import:R0603")
      (libsource (lib "eagle-import") (part "R-EU_R0603"))
    )
    (comp (ref "R16")
      (value "270")
      (footprint "eagle-import:R0603")
      (libsource (lib "eagle-import") (part "resistor_R-EU_R0603"))
    )
    (comp (ref "R17")
      (value "680")
      (footprint "eagle-import:R0603")
      (libsource (lib "eagle-import") (part "resistor_R-EU_R0603"))
    )
    (comp (ref "R18")
      (value "1k")
      (footprint "eagle-import:R0603")
      (libsource (lib "eagle-import") (part "resistor_R-EU_R0603"))
    )
    (comp (ref "R19")
      (value "2k")
      (footprint "eagle-import:R0603")
      (libsource (lib "eagle-import") (part "resistor_R-EU_R0603"))
    )
    (comp (ref "R80")
      (value "470")
      (footprint "eagle-import:R0603")
      (libsource (lib "eagle-import") (part "resistor_R-EU_R0603"))
    )
    (comp (ref "R81")
      (value "2.2k")
      (footprint "eagle-import:R0603")
      (libsource (lib "eagle-import") (part "resistor_R-EU_R0603"))
    )
    (comp (ref "R82")
      (value "47k")
      (footprint "eagle-import:R0603")
      (libsource (lib "eagle-import") (part "R-EU_R0603"))
    )
    (comp (ref "R83")
      (value "47k")
      (footprint "eagle-import:R0603")
      (libsource (lib "eagle-import") (part "R-EU_R0603"))
    )
    (comp (ref "R84")
      (value "47k")
      (footprint "eagle-import:R0603")
      (libsource (lib "eagle-import") (part "R-EU_R0603"))
    )
    (comp (ref "RTC")
      (value "M03LOCK")
      (footprint "eagle-import:1X03_LOCK")
      (libsource (lib "eagle-import") (part "M03LOCK"))
    )
    (comp (ref "SWITCHS")
      (value "MC15-GF-3.81-LR_4")
      (footprint "eagle-import:CON_3.81_LR_4")
      (libsource (lib "eagle-import") (part "MC15-GF-3.81-LR_4"))
    )
    (comp (ref "U3V3L")
      (value "TSR_1-2433")
      (footprint "eagle-import:TSR1")
      (libsource (lib "eagle-import") (part "TSR_1-24XX"))
    )
    (comp (ref "U5VL")
      (value "TSR_1-2450")
      (footprint "eagle-import:TSR1")
      (libsource (lib "eagle-import") (part "TSR_1-24XX"))
    )
    (comp (ref "U12VL")
      (value "TSR_1-24120")
      (footprint "eagle-import:TSR1")
      (libsource (lib "eagle-import") (part "TSR_1-24XX"))
    )
    (comp (ref "UVP1")
      (value "PTN78060W")
      (footprint "eagle-import:PTN78060")
      (libsource (lib "eagle-import") (part "PTN78060W"))
    )
    (comp (ref "UVP2")
      (value "PTN78060W")
      (footprint "eagle-import:PTN78060")
      (libsource (lib "eagle-import") (part "PTN78060W"))
    )
    (comp (ref "UVP3")
      (value "PTN78060H")
      (footprint "eagle-import:PTN78060")
      (libsource (lib "eagle-import") (part "PTN78060W"))
    )
    (comp (ref "VCC1")
      (value "CON_3.5_2")
      (footprint "eagle-import:CON_3.5_2")
      (libsource (lib "eagle-import") (part "CON_3.5_2"))
    )
    (comp (ref "VCC2")
      (value "CON_3.5_2")
      (footprint "eagle-import:CON_3.5_2")
      (libsource (lib "eagle-import") (part "CON_3.5_2"))
    )
    (comp (ref "VCC3")
      (value "CON_3.5_2")
      (footprint "eagle-import:CON_3.5_2")
      (libsource (lib "eagle-import") (part "CON_3.5_2"))
    )
    (comp (ref "VP1")
      (value "CON_3.5_2")
      (footprint "eagle-import:CON_3.5_2")
      (libsource (lib "eagle-import") (part "CON_3.5_2"))
    )
    (comp (ref "VP2")
      (value "CON_3.5_2")
      (footprint "eagle-import:CON_3.5_2")
      (libsource (lib "eagle-import") (part "CON_3.5_2"))
    )
    (comp (ref "VP3")
      (value "CON_3.5_2")
      (footprint "eagle-import:CON_3.5_2")
      (libsource (lib "eagle-import") (part "CON_3.5_2"))
    )
    (comp (ref "ENC1")
      (value "CON_1.27_4")
      (footprint "eagle-import:CON_1.27_4")
      (libsource (lib "eagle-import") (part "CON_1.27_4"))
    )
    (comp (ref "ENC2")
      (value "CON_1.27_4")
      (footprint "eagle-import:CON_1.27_4")
      (libsource (lib "eagle-import") (part "CON_1.27_4"))
    )
    (comp (ref "END1")
      (value "CON_1.27_4")
      (footprint "eagle-import:CON_1.27_4")
      (libsource (lib "eagle-import") (part "CON_1.27_4"))
    )
    (comp (ref "END2")
      (value "CON_1.27_4")
      (footprint "eagle-import:CON_1.27_4")
      (libsource (lib "eagle-import") (part "CON_1.27_4"))
    )
    (comp (ref "END3")
      (value "CON_1.27_4")
      (footprint "eagle-import:CON_1.27_4")
      (libsource (lib "eagle-import") (part "CON_1.27_4"))
    )
    (comp (ref "END4")
      (value "CON_1.27_4")
      (footprint "eagle-import:CON_1.27_4")
      (libsource (lib "eagle-import") (part "CON_1.27_4"))
    )
    (comp (ref "END5")
      (value "CON_1.27_4")
      (footprint "eagle-import:CON_1.27_4")
      (libsource (lib "eagle-import") (part "CON_1.27_4"))
    )
    (comp (ref "END6")
      (value "CON_1.27_4")
      (footprint "eagle-import:CON_1.27_4")
      (libsource (lib "eagle-import") (part "CON_1.27_4"))
    )
    (comp (ref "END7")
      (value "CON_1.27_4")
      (footprint "eagle-import:CON_1.27_4")
      (libsource (lib "eagle-import") (part "CON_1.27_4"))
    )
    (comp (ref "END8")
      (value "CON_1.27_4")
      (footprint "eagle-import:CON_1.27_4")
      (libsource (lib "eagle-import") (part "CON_1.27_4"))
    )
    (comp (ref "IND1")
      (value "CON_1.27_4")
      (footprint "eagle-import:CON_1.27_4")
      (libsource (lib "eagle-import") (part "CON_1.27_4"))
    )
    (comp (ref "IND2")
      (value "CON_1.27_4")
      (footprint "eagle-import:CON_1.27_4")
      (libsource (lib "eagle-import") (part "CON_1.27_4"))
    )
    (comp (ref "IND3")
      (value "CON_1.27_4")
      (footprint "eagle-import:CON_1.27_4")
      (libsource (lib "eagle-import") (part "CON_1.27_4"))
    )
    (comp (ref "IND4")
      (value "CON_1.27_4")
      (footprint "eagle-import:CON_1.27_4")
      (libsource (lib "eagle-import") (part "CON_1.27_4"))
    )
    (comp (ref "IND5")
      (value "CON_1.27_4")
      (footprint "eagle-import:CON_1.27_4")
      (libsource (lib "eagle-import") (part "CON_1.27_4"))
    )
    (comp (ref "IND6")
      (value "CON_1.27_4")
      (footprint "eagle-import:CON_1.27_4")
      (libsource (lib "eagle-import") (part "CON_1.27_4"))
    )
    (comp (ref "IND7")
      (value "CON_1.27_4")
      (footprint "eagle-import:CON_1.27_4")
      (libsource (lib "eagle-import") (part "CON_1.27_4"))
    )
    (comp (ref "IND8")
      (value "CON_1.27_4")
      (footprint "eagle-import:CON_1.27_4")
      (libsource (lib "eagle-import") (part "CON_1.27_4"))
    )
    (comp (ref "IND9")
      (value "CON_1.27_4")
      (footprint "eagle-import:CON_1.27_4")
      (libsource (lib "eagle-import") (part "CON_1.27_4"))
    )
    (comp (ref "IND10")
      (value "CON_1.27_4")
      (footprint "eagle-import:CON_1.27_4")
      (libsource (lib "eagle-import") (part "CON_1.27_4"))
    )
    (comp (ref "OPTO9")
      (value "EL3H4-G")
      (footprint "eagle-import:SSOP_4")
      (libsource (lib "eagle-import") (part "EL3H4-G"))
    )
    (comp (ref "OPTO10")
      (value "EL3H4-G")
      (footprint "eagle-import:SSOP_4")
      (libsource (lib "eagle-import") (part "EL3H4-G"))
    )
    (comp (ref "OPTO11")
      (value "EL3H4-G")
      (footprint "eagle-import:SSOP_4")
      (libsource (lib "eagle-import") (part "EL3H4-G"))
    )
    (comp (ref "OPTO12")
      (value "EL3H4-G")
      (footprint "eagle-import:SSOP_4")
      (libsource (lib "eagle-import") (part "EL3H4-G"))
    )
    (comp (ref "OPTO13")
      (value "EL3H4-G")
      (footprint "eagle-import:SSOP_4")
      (libsource (lib "eagle-import") (part "EL3H4-G"))
    )
    (comp (ref "OPTO14")
      (value "EL3H4-G")
      (footprint "eagle-import:SSOP_4")
      (libsource (lib "eagle-import") (part "EL3H4-G"))
    )
    (comp (ref "OPTO15")
      (value "EL3H4-G")
      (footprint "eagle-import:SSOP_4")
      (libsource (lib "eagle-import") (part "EL3H4-G"))
    )
    (comp (ref "OPTO16")
      (value "EL3H4-G")
      (footprint "eagle-import:SSOP_4")
      (libsource (lib "eagle-import") (part "EL3H4-G"))
    )
    (comp (ref "OPTO17")
      (value "EL3H4-G")
      (footprint "eagle-import:SSOP_4")
      (libsource (lib "eagle-import") (part "EL3H4-G"))
    )
    (comp (ref "OPTO18")
      (value "EL3H4-G")
      (footprint "eagle-import:SSOP_4")
      (libsource (lib "eagle-import") (part "EL3H4-G"))
    )
    (comp (ref "R52")
      (value "1k")
      (footprint "eagle-import:R0603")
      (libsource (lib "eagle-import") (part "resistor_R-EU_R0603"))
    )
    (comp (ref "R53")
      (value "330")
      (footprint "eagle-import:R0603")
      (libsource (lib "eagle-import") (part "resistor_R-EU_R0603"))
    )
    (comp (ref "R54")
      (value "1k")
      (footprint "eagle-import:R0603")
      (libsource (lib "eagle-import") (part "resistor_R-EU_R0603"))
    )
    (comp (ref "R55")
      (value "330")
      (footprint "eagle-import:R0603")
      (libsource (lib "eagle-import") (part "resistor_R-EU_R0603"))
    )
    (comp (ref "R56")
      (value "1k")
      (footprint "eagle-import:R0603")
      (libsource (lib "eagle-import") (part "resistor_R-EU_R0603"))
    )
    (comp (ref "R57")
      (value "330")
      (footprint "eagle-import:R0603")
      (libsource (lib "eagle-import") (part "resistor_R-EU_R0603"))
    )
    (comp (ref "R58")
      (value "1k")
      (footprint "eagle-import:R0603")
      (libsource (lib "eagle-import") (part "resistor_R-EU_R0603"))
    )
    (comp (ref "R59")
      (value "330")
      (footprint "eagle-import:R0603")
      (libsource (lib "eagle-import") (part "resistor_R-EU_R0603"))
    )
    (comp (ref "R60")
      (value "1k")
      (footprint "eagle-import:R0603")
      (libsource (lib "eagle-import") (part "resistor_R-EU_R0603"))
    )
    (comp (ref "R61")
      (value "330")
      (footprint "eagle-import:R0603")
      (libsource (lib "eagle-import") (part "resistor_R-EU_R0603"))
    )
    (comp (ref "R62")
      (value "1k")
      (footprint "eagle-import:R0603")
      (libsource (lib "eagle-import") (part "resistor_R-EU_R0603"))
    )
    (comp (ref "R63")
      (value "330")
      (footprint "eagle-import:R0603")
      (libsource (lib "eagle-import") (part "resistor_R-EU_R0603"))
    )
    (comp (ref "R64")
      (value "10k")
      (footprint "eagle-import:R0603")
      (libsource (lib "eagle-import") (part "resistor_R-EU_R0603"))
    )
    (comp (ref "R65")
      (value "10k")
      (footprint "eagle-import:R0603")
      (libsource (lib "eagle-import") (part "resistor_R-EU_R0603"))
    )
    (comp (ref "R66")
      (value "10k")
      (footprint "eagle-import:R0603")
      (libsource (lib "eagle-import") (part "resistor_R-EU_R0603"))
    )
    (comp (ref "R67")
      (value "10k")
      (footprint "eagle-import:R0603")
      (libsource (lib "eagle-import") (part "resistor_R-EU_R0603"))
    )
    (comp (ref "R68")
      (value "1k")
      (footprint "eagle-import:R0603")
      (libsource (lib "eagle-import") (part "resistor_R-EU_R0603"))
    )
    (comp (ref "R69")
      (value "330")
      (footprint "eagle-import:R0603")
      (libsource (lib "eagle-import") (part "resistor_R-EU_R0603"))
    )
    (comp (ref "R70")
      (value "1k")
      (footprint "eagle-import:R0603")
      (libsource (lib "eagle-import") (part "resistor_R-EU_R0603"))
    )
    (comp (ref "R71")
      (value "330")
      (footprint "eagle-import:R0603")
      (libsource (lib "eagle-import") (part "resistor_R-EU_R0603"))
    )
    (comp (ref "R72")
      (value "1k")
      (footprint "eagle-import:R0603")
      (libsource (lib "eagle-import") (part "resistor_R-EU_R0603"))
    )
    (comp (ref "R73")
      (value "330")
      (footprint "eagle-import:R0603")
      (libsource (lib "eagle-import") (part "resistor_R-EU_R0603"))
    )
    (comp (ref "R74")
      (value "1k")
      (footprint "eagle-import:R0603")
      (libsource (lib "eagle-import") (part "resistor_R-EU_R0603"))
    )
    (comp (ref "R75")
      (value "330")
      (footprint "eagle-import:R0603")
      (libsource (lib "eagle-import") (part "resistor_R-EU_R0603"))
    )
    (comp (ref "RS485")
      (value "JST-SHR-8V")
      (footprint "eagle-import:JST-SHR-08V")
      (libsource (lib "eagle-import") (part "JST-SHR-8V"))
    )
    (comp (ref "C1")
      (value "100nF")
      (footprint "eagle-import:C0603")
      (libsource (lib "eagle-import") (part "C-EUC0603"))
    )
    (comp (ref "C2")
      (value "18 pF")
      (footprint "eagle-import:C0603")
      (libsource (lib "eagle-import") (part "C-EUC0603"))
    )
    (comp (ref "C3")
      (value "18 pF")
      (footprint "eagle-import:C0603")
      (libsource (lib "eagle-import") (part "C-EUC0603"))
    )
    (comp (ref "C4")
      (value "100nF")
      (footprint "eagle-import:C0603")
      (libsource (lib "eagle-import") (part "C-EUC0603"))
    )
    (comp (ref "C5")
      (value "100nF")
      (footprint "eagle-import:C0603")
      (libsource (lib "eagle-import") (part "C-EUC0603"))
    )
    (comp (ref "C6")
      (value "100nF")
      (footprint "eagle-import:C0603")
      (libsource (lib "eagle-import") (part "C-EUC0603"))
    )
    (comp (ref "C7")
      (value "100nF")
      (footprint "eagle-import:C0603")
      (libsource (lib "eagle-import") (part "C-EUC0603"))
    )
    (comp (ref "C8")
      (value "100nF")
      (footprint "eagle-import:C0603")
      (libsource (lib "eagle-import") (part "C-EUC0603"))
    )
    (comp (ref "C9")
      (value "10nF")
      (footprint "eagle-import:C0603")
      (libsource (lib "eagle-import") (part "C-EUC0603"))
    )
    (comp (ref "C10")
      (value "10nF")
      (footprint "eagle-import:C0603")
      (libsource (lib "eagle-import") (part "C-EUC0603"))
    )
    (comp (ref "C11")
      (value "1uF")
      (footprint "eagle-import:C0805")
      (libsource (lib "eagle-import") (part "C-EUC0805"))
    )
    (comp (ref "C12")
      (value "2.2uF")
      (footprint "eagle-import:C0805")
      (libsource (lib "eagle-import") (part "C-EUC0805"))
    )
    (comp (ref "C13")
      (value "2.2uF")
      (footprint "eagle-import:C0805")
      (libsource (lib "eagle-import") (part "C-EUC0805"))
    )
    (comp (ref "CX1")
      (value "XTAL_5X3")
      (footprint "eagle-import:CRYSTAL-OSC-SMD-5X3")
      (libsource (lib "eagle-import") (part "XTAL_5X3"))
    )
    (comp (ref "LED1")
      (value "ASMB-MTB0-0A3A2")
      (footprint "eagle-import:PLCC4")
      (libsource (lib "eagle-import") (part "ASMB-MTB0-0A3A2"))
    )
    (comp (ref "LOGO_IGREBOT")
      (value "LOGO_IGREBOT12X2MM")
      (footprint "eagle-import:IGREBOT_12X2MM")
      (libsource (lib "eagle-import") (part "LOGO_IGREBOT12X2MM"))
    )
    (comp (ref "LOGO_LAYERS")
      (value "LAYERS_CHECK4_LAYERS")
      (footprint "eagle-import:LAYERS_CHECK_4")
      (libsource (lib "eagle-import") (part "LAYERS_CHECK4_LAYERS"))
    )
    (comp (ref "R1")
      (value "270")
      (footprint "eagle-import:R0603")
      (libsource (lib "eagle-import") (part "resistor_R-EU_R0603"))
    )
    (comp (ref "R2")
      (value "47")
      (footprint "eagle-import:R0603")
      (libsource (lib "eagle-import") (part "resistor_R-EU_R0603"))
    )
    (comp (ref "R3")
      (value "47")
      (footprint "eagle-import:R0603")
      (libsource (lib "eagle-import") (part "resistor_R-EU_R0603"))
    )
    (comp (ref "R4")
      (value "47k")
      (footprint "eagle-import:R0603")
      (libsource (lib "eagle-import") (part "resistor_R-EU_R0603"))
    )
    (comp (ref "SJ1")
      (value "SOLDERJUMPERNC2")
      (footprint "eagle-import:SJ_2S-NOTRACE")
      (libsource (lib "eagle-import") (part "SOLDERJUMPERNC2"))
    )
    (comp (ref "SJ2")
      (value "SOLDERJUMPERNC2")
      (footprint "eagle-import:SJ_2S-NOTRACE")
      (libsource (lib "eagle-import") (part "SOLDERJUMPERNC2"))
    )
    (comp (ref "STM32")
      (value "STM32F746VG")
      (footprint "eagle-import:LQFP_100")
      (libsource (lib "eagle-import") (part "STM32F746VG"))
    )
    (comp (ref "SWD")
      (value "M06LOCK")
      (footprint "eagle-import:1X06_LOCK")
      (libsource (lib "eagle-import") (part "M06LOCK"))
    )
    (comp (ref "USB")
      (value "MINI-USB-32005-201")
      (footprint "eagle-import:32005-201")
      (libsource (lib "eagle-import") (part "MINI-USB-32005-201"))
    )
    (comp (ref "VREF")
      (value "REF3030")
      (footprint "eagle-import:SOT23")
      (fields (field (name "MF") "MAXIM") (field (name "MPN") "MAX6520EUR-T"))
      (libsource (lib "eagle-import") (part "MAX6520"))
    )
    (comp (ref "C45")
      (value "100nF")
      (footprint "eagle-import:C0603K")
      (libsource (lib "eagle-import") (part "resistor_C-EUC0603K"))
    )
    (comp (ref "C46")
      (value "100nF")
      (footprint "eagle-import:C0603")
      (libsource (lib "eagle-import") (part "C-EUC0603"))
    )
    (comp (ref "HMI")
      (value "HE10_V_16")
      (footprint "eagle-import:CON_2X_2.54_V_16")
      (libsource (lib "eagle-import") (part "HE10_V_16"))
    )
    (comp (ref "R76")
      (value "120")
      (footprint "eagle-import:R0603")
      (libsource (lib "eagle-import") (part "R-EU_R0603"))
    )
    (comp (ref "R77")
      (value "120")
      (footprint "eagle-import:R0603")
      (libsource (lib "eagle-import") (part "R-EU_R0603"))
    )
    (comp (ref "R78")
      (value "10k")
      (footprint "eagle-import:R0603")
      (libsource (lib "eagle-import") (part "R-EU_R0603"))
    )
    (comp (ref "R79")
      (value "120")
      (footprint "eagle-import:R0603")
      (libsource (lib "eagle-import") (part "R-EU_R0603"))
    )
    (comp (ref "SJ3")
      (value "SOLDERJUMPERNC2")
      (footprint "eagle-import:SJ_2S-NOTRACE")
      (libsource (lib "eagle-import") (part "SOLDERJUMPERNC2"))
    )
    (comp (ref "SJ4")
      (value "SOLDERJUMPERNC2")
      (footprint "eagle-import:SJ_2S-NOTRACE")
      (libsource (lib "eagle-import") (part "SOLDERJUMPERNC2"))
    )
    (comp (ref "SJ5")
      (value "SOLDERJUMPERNC2")
      (footprint "eagle-import:SJ_2S-NOTRACE")
      (libsource (lib "eagle-import") (part "SOLDERJUMPERNC2"))
    )
    (comp (ref "UART")
      (value "M05LOCK")
      (footprint "eagle-import:1X05_LOCK")
      (libsource (lib "eagle-import") (part "M05LOCK"))
    )
    (comp (ref "UCAN")
      (value "SN65HVD230D")
      (footprint "eagle-import:SO-08")
      (libsource (lib "eagle-import") (part "MCP2551"))
    )
    (comp (ref "URS485")
      (value "SN65HVD1476-DGS")
      (footprint "eagle-import:MSOP-10")
      (libsource (lib "eagle-import") (part "SN65HVD1476-DGS"))
    )
  )
  (nets
    (net (code "1") (name "+3V3L") (class "Default")
      (node (ref "C27") (pin "1") (pinfunction "1_1") (pintype "passive"))
      (node (ref "C4") (pin "1") (pinfunction "1_1") (pintype "passive"))
      (node (ref "C43") (pin "1") (pinfunction "1_1") (pintype "passive"))
      (node (ref "C44") (pin "1") (pinfunction "1_1") (pintype "passive"))
      (node (ref "C45") (pin "1") (pinfunction "1_1") (pintype "passive"))
      (node (ref "C46") (pin "1") (pinfunction "1_1") (pintype "passive"))
      (node (ref "C5") (pin "1") (pinfunction "1_1") (pintype "passive"))
      (node (ref "C6") (pin "1") (pinfunction "1_1") (pintype "passive"))
      (node (ref "C7") (pin "1") (pinfunction "1_1") (pintype "passive"))
      (node (ref "C8") (pin "1") (pinfunction "1_1") (pintype "passive"))
      (node (ref "C9") (pin "1") (pinfunction "1_1") (pintype "passive"))
      (node (ref "END1") (pin "1") (pinfunction "1_1") (pintype "bidirectional"))
      (node (ref "END2") (pin "1") (pinfunction "1_1") (pintype "bidirectional"))
      (node (ref "END3") (pin "1") (pinfunction "1_1") (pintype "bidirectional"))
      (node (ref "END4") (pin "1") (pinfunction "1_1") (pintype "bidirectional"))
      (node (ref "END5") (pin "1") (pinfunction "1_1") (pintype "bidirectional"))
      (node (ref "END6") (pin "1") (pinfunction "1_1") (pintype "bidirectional"))
      (node (ref "END7") (pin "1") (pinfunction "1_1") (pintype "bidirectional"))
      (node (ref "END8") (pin "1") (pinfunction "1_1") (pintype "bidirectional"))
      (node (ref "IBAT") (pin "5") (pinfunction "V+_5") (pintype "bidirectional"))
      (node (ref "IP1") (pin "5") (pinfunction "V+_5") (pintype "bidirectional"))
      (node (ref "IP2") (pin "5") (pinfunction "V+_5") (pintype "bidirectional"))
      (node (ref "IP3") (pin "5") (pinfunction "V+_5") (pintype "bidirectional"))
      (node (ref "LED1") (pin "1") (pinfunction "A_1") (pintype "bidirectional"))
      (node (ref "LED4") (pin "A") (pinfunction "A_A") (pintype "passive"))
      (node (ref "OPA1") (pin "4") (pinfunction "V+_4") (pintype "power_in"))
      (node (ref "OPA2") (pin "4") (pinfunction "V+_4") (pintype "power_in"))
      (node (ref "R44") (pin "2") (pinfunction "2_2") (pintype "passive"))
      (node (ref "R53") (pin "2") (pinfunction "2_2") (pintype "passive"))
      (node (ref "R55") (pin "2") (pinfunction "2_2") (pintype "passive"))
      (node (ref "R57") (pin "2") (pinfunction "2_2") (pintype "passive"))
      (node (ref "R59") (pin "2") (pinfunction "2_2") (pintype "passive"))
      (node (ref "R61") (pin "2") (pinfunction "2_2") (pintype "passive"))
      (node (ref "R63") (pin "2") (pinfunction "2_2") (pintype "passive"))
      (node (ref "R64") (pin "2") (pinfunction "2_2") (pintype "passive"))
      (node (ref "R65") (pin "2") (pinfunction "2_2") (pintype "passive"))
      (node (ref "R66") (pin "2") (pinfunction "2_2") (pintype "passive"))
      (node (ref "R67") (pin "2") (pinfunction "2_2") (pintype "passive"))
      (node (ref "R69") (pin "2") (pinfunction "2_2") (pintype "passive"))
      (node (ref "R71") (pin "2") (pinfunction "2_2") (pintype "passive"))
      (node (ref "R73") (pin "2") (pinfunction "2_2") (pintype "passive"))
      (node (ref "R75") (pin "2") (pinfunction "2_2") (pintype "passive"))
      (node (ref "R82") (pin "2") (pinfunction "2_2") (pintype "passive"))
      (node (ref "R83") (pin "2") (pinfunction "2_2") (pintype "passive"))
      (node (ref "R84") (pin "2") (pinfunction "2_2") (pintype "passive"))
      (node (ref "RTC") (pin "1") (pinfunction "1_1") (pintype "passive"))
      (node (ref "STM32") (pin "100") (pinfunction "VDD_100") (pintype "bidirectional"))
      (node (ref "STM32") (pin "11") (pinfunction "VDD_11") (pintype "bidirectional"))
      (node (ref "STM32") (pin "21") (pinfunction "VDDA_21") (pintype "bidirectional"))
      (node (ref "STM32") (pin "27") (pinfunction "VDD_27") (pintype "bidirectional"))
      (node (ref "STM32") (pin "50") (pinfunction "VDD_50") (pintype "bidirectional"))
      (node (ref "STM32") (pin "75") (pinfunction "VDD_75") (pintype "bidirectional"))
      (node (ref "SWD") (pin "1") (pinfunction "1_1") (pintype "passive"))
      (node (ref "U3V3L") (pin "3") (pinfunction "VO_3") (pintype "power_in"))
      (node (ref "UCAN") (pin "3") (pinfunction "VDD_3") (pintype "bidirectional"))
      (node (ref "URS485") (pin "10") (pinfunction "VCC_10") (pintype "bidirectional"))
      (node (ref "VCC3") (pin "1") (pinfunction "1_1") (pintype "bidirectional"))
      (node (ref "VREF") (pin "1") (pinfunction "IN_1") (pintype "input"))
    )
    (net (code "2") (name "+5VL") (class "Default")
      (node (ref "C26") (pin "1") (pinfunction "1_1") (pintype "passive"))
      (node (ref "C39") (pin "1") (pinfunction "1_1") (pintype "passive"))
      (node (ref "C40") (pin "1") (pinfunction "1_1") (pintype "passive"))
      (node (ref "C41") (pin "1") (pinfunction "1_1") (pintype "passive"))
      (node (ref "C42") (pin "1") (pinfunction "1_1") (pintype "passive"))
      (node (ref "CEL1") (pin "7") (pinfunction "V+_7") (pintype "bidirectional"))
      (node (ref "CEL2") (pin "7") (pinfunction "V+_7") (pintype "bidirectional"))
      (node (ref "CEL3") (pin "7") (pinfunction "V+_7") (pintype "bidirectional"))
      (node (ref "CEL4") (pin "7") (pinfunction "V+_7") (pintype "bidirectional"))
      (node (ref "ENC1") (pin "1") (pinfunction "1_1") (pintype "bidirectional"))
      (node (ref "ENC2") (pin "1") (pinfunction "1_1") (pintype "bidirectional"))
      (node (ref "HMI") (pin "1") (pinfunction "1_1") (pintype "bidirectional"))
      (node (ref "LED8") (pin "A") (pinfunction "A_A") (pintype "passive"))
      (node (ref "RS485") (pin "1") (pinfunction "1_1") (pintype "passive"))
      (node (ref "U5VL") (pin "3") (pinfunction "VO_3") (pintype "power_in"))
      (node (ref "VCC2") (pin "1") (pinfunction "1_1") (pintype "bidirectional"))
    )
    (net (code "3") (name "+12VL") (class "Default")
      (node (ref "C25") (pin "1") (pinfunction "1_1") (pintype "passive"))
      (node (ref "IND1") (pin "1") (pinfunction "1_1") (pintype "bidirectional"))
      (node (ref "IND10") (pin "1") (pinfunction "1_1") (pintype "bidirectional"))
      (node (ref "IND2") (pin "1") (pinfunction "1_1") (pintype "bidirectional"))
      (node (ref "IND3") (pin "1") (pinfunction "1_1") (pintype "bidirectional"))
      (node (ref "IND4") (pin "1") (pinfunction "1_1") (pintype "bidirectional"))
      (node (ref "IND5") (pin "1") (pinfunction "1_1") (pintype "bidirectional"))
      (node (ref "IND6") (pin "1") (pinfunction "1_1") (pintype "bidirectional"))
      (node (ref "IND7") (pin "1") (pinfunction "1_1") (pintype "bidirectional"))
      (node (ref "IND8") (pin "1") (pinfunction "1_1") (pintype "bidirectional"))
      (node (ref "IND9") (pin "1") (pinfunction "1_1") (pintype "bidirectional"))
      (node (ref "LED9") (pin "A") (pinfunction "A_A") (pintype "passive"))
      (node (ref "U12VL") (pin "3") (pinfunction "VO_3") (pintype "power_in"))
      (node (ref "VCC1") (pin "1") (pinfunction "1_1") (pintype "bidirectional"))
    )
    (net (code "4") (name "+VBATL") (class "Default")
      (node (ref "C24") (pin "1") (pinfunction "1_1") (pintype "passive"))
      (node (ref "IBAT") (pin "4") (pinfunction "VIN-_4") (pintype "bidirectional"))
      (node (ref "R5") (pin "2") (pinfunction "2_2") (pintype "passive"))
      (node (ref "SWITCHS") (pin "2") (pinfunction "2_2") (pintype "bidirectional"))
      (node (ref "U12VL") (pin "1") (pinfunction "VI_1") (pintype "power_in"))
      (node (ref "U3V3L") (pin "1") (pinfunction "VI_1") (pintype "power_in"))
      (node (ref "U5VL") (pin "1") (pinfunction "VI_1") (pintype "power_in"))
    )
    (net (code "5") (name "+VBATP") (class "Default")
      (node (ref "C14") (pin "+") (pinfunction "+_+") (pintype "passive"))
      (node (ref "C15") (pin "1") (pinfunction "1_1") (pintype "passive"))
      (node (ref "C18") (pin "1") (pinfunction "1_1") (pintype "passive"))
      (node (ref "C21") (pin "1") (pinfunction "1_1") (pintype "passive"))
      (node (ref "SWITCHS") (pin "1") (pinfunction "1_1") (pintype "bidirectional"))
      (node (ref "UMOT") (pin "11") (pinfunction "VM_11") (pintype "bidirectional"))
      (node (ref "UMOT") (pin "12") (pinfunction "VM_12") (pintype "bidirectional"))
      (node (ref "UVP1") (pin "2") (pinfunction "VI_2") (pintype "power_in"))
      (node (ref "UVP2") (pin "2") (pinfunction "VI_2") (pintype "power_in"))
      (node (ref "UVP3") (pin "2") (pinfunction "VI_2") (pintype "power_in"))
    )
    (net (code "6") (name "+VP1") (class "Default")
      (node (ref "ASV1") (pin "1") (pinfunction "1_1") (pintype "bidirectional"))
      (node (ref "ASV2") (pin "1") (pinfunction "1_1") (pintype "bidirectional"))
      (node (ref "ASV3") (pin "1") (pinfunction "1_1") (pintype "bidirectional"))
      (node (ref "ASV4") (pin "1") (pinfunction "1_1") (pintype "bidirectional"))
      (node (ref "ASV5") (pin "1") (pinfunction "1_1") (pintype "bidirectional"))
      (node (ref "ASV6") (pin "1") (pinfunction "1_1") (pintype "bidirectional"))
      (node (ref "ASV7") (pin "1") (pinfunction "1_1") (pintype "bidirectional"))
      (node (ref "ASV8") (pin "1") (pinfunction "1_1") (pintype "bidirectional"))
      (node (ref "IP1") (pin "4") (pinfunction "VIN-_4") (pintype "bidirectional"))
      (node (ref "LED5") (pin "A") (pinfunction "A_A") (pintype "passive"))
      (node (ref "R35") (pin "2") (pinfunction "2_2") (pintype "passive"))
      (node (ref "R37") (pin "2") (pinfunction "2_2") (pintype "passive"))
      (node (ref "R39") (pin "2") (pinfunction "2_2") (pintype "passive"))
      (node (ref "R41") (pin "2") (pinfunction "2_2") (pintype "passive"))
      (node (ref "R43") (pin "2") (pinfunction "2_2") (pintype "passive"))
      (node (ref "R46") (pin "2") (pinfunction "2_2") (pintype "passive"))
      (node (ref "R49") (pin "2") (pinfunction "2_2") (pintype "passive"))
      (node (ref "R51") (pin "2") (pinfunction "2_2") (pintype "passive"))
      (node (ref "R6") (pin "2") (pinfunction "2_2") (pintype "passive"))
      (node (ref "VP1") (pin "1") (pinfunction "1_1") (pintype "bidirectional"))
    )
    (net (code "7") (name "+VP2") (class "Default")
      (node (ref "DSV1") (pin "2") (pinfunction "2_2") (pintype "bidirectional"))
      (node (ref "DSV2") (pin "2") (pinfunction "2_2") (pintype "bidirectional"))
      (node (ref "DSV3") (pin "1") (pinfunction "1_1") (pintype "bidirectional"))
      (node (ref "IP2") (pin "4") (pinfunction "VIN-_4") (pintype "bidirectional"))
      (node (ref "LED6") (pin "A") (pinfunction "A_A") (pintype "passive"))
      (node (ref "R10") (pin "2") (pinfunction "2_2") (pintype "passive"))
      (node (ref "VP2") (pin "1") (pinfunction "1_1") (pintype "bidirectional"))
    )
    (net (code "8") (name "+VP3") (class "Default")
      (node (ref "IP3") (pin "4") (pinfunction "VIN-_4") (pintype "bidirectional"))
      (node (ref "LED7") (pin "A") (pinfunction "A_A") (pintype "passive"))
      (node (ref "R13") (pin "2") (pinfunction "2_2") (pintype "passive"))
      (node (ref "VP3") (pin "1") (pinfunction "1_1") (pintype "bidirectional"))
    )
    (net (code "9") (name "ADC_CEL1") (class "Default")
      (node (ref "CEL1") (pin "6") (pinfunction "OUT_6") (pintype "bidirectional"))
      (node (ref "STM32") (pin "32") (pinfunction "PC4_32") (pintype "bidirectional"))
    )
    (net (code "10") (name "ADC_CEL2") (class "Default")
      (node (ref "CEL2") (pin "6") (pinfunction "OUT_6") (pintype "bidirectional"))
      (node (ref "STM32") (pin "33") (pinfunction "PC5_33") (pintype "bidirectional"))
    )
    (net (code "11") (name "ADC_CEL3") (class "Default")
      (node (ref "CEL3") (pin "6") (pinfunction "OUT_6") (pintype "bidirectional"))
      (node (ref "STM32") (pin "34") (pinfunction "PB0_34") (pintype "bidirectional"))
    )
    (net (code "12") (name "ADC_CEL4") (class "Default")
      (node (ref "CEL4") (pin "6") (pinfunction "OUT_6") (pintype "bidirectional"))
      (node (ref "STM32") (pin "35") (pinfunction "PB1_35") (pintype "bidirectional"))
    )
    (net (code "13") (name "ADC_IBAT") (class "Default")
      (node (ref "C34") (pin "1") (pinfunction "1_1") (pintype "passive"))
      (node (ref "R25") (pin "2") (pinfunction "2_2") (pintype "passive"))
      (node (ref "STM32") (pin "17") (pinfunction "PC2_17") (pintype "bidirectional"))
    )
    (net (code "14") (name "ADC_IMOT1") (class "Default")
      (node (ref "C36") (pin "1") (pinfunction "1_1") (pintype "passive"))
      (node (ref "R27") (pin "2") (pinfunction "2_2") (pintype "passive"))
      (node (ref "STM32") (pin "30") (pinfunction "PA6_30") (pintype "bidirectional"))
    )
    (net (code "15") (name "ADC_IMOT2") (class "Default")
      (node (ref "C38") (pin "1") (pinfunction "1_1") (pintype "passive"))
      (node (ref "R31") (pin "2") (pinfunction "2_2") (pintype "passive"))
      (node (ref "STM32") (pin "31") (pinfunction "PA7_31") (pintype "bidirectional"))
    )
    (net (code "16") (name "ADC_IP1") (class "Default")
      (node (ref "C30") (pin "1") (pinfunction "1_1") (pintype "passive"))
      (node (ref "R21") (pin "2") (pinfunction "2_2") (pintype "passive"))
      (node (ref "STM32") (pin "18") (pinfunction "PC3_18") (pintype "bidirectional"))
    )
    (net (code "17") (name "ADC_IP2") (class "Default")
      (node (ref "C31") (pin "1") (pinfunction "1_1") (pintype "passive"))
      (node (ref "R22") (pin "2") (pinfunction "2_2") (pintype "passive"))
      (node (ref "STM32") (pin "28") (pinfunction "PA4_28") (pintype "bidirectional"))
    )
    (net (code "18") (name "ADC_IP3") (class "Default")
      (node (ref "C33") (pin "1") (pinfunction "1_1") (pintype "passive"))
      (node (ref "R24") (pin "2") (pinfunction "2_2") (pintype "passive"))
      (node (ref "STM32") (pin "29") (pinfunction "PA5_29") (pintype "bidirectional"))
    )
    (net (code "19") (name "ADC_VREF") (class "Default")
      (node (ref "C10") (pin "1") (pinfunction "1_1") (pintype "passive"))
      (node (ref "C11") (pin "1") (pinfunction "1_1") (pintype "passive"))
      (node (ref "STM32") (pin "20") (pinfunction "VREF+_20") (pintype "bidirectional"))
      (node (ref "VREF") (pin "2") (pinfunction "OUT_2") (pintype "output"))
    )
    (net (code "20") (name "ASV1_OUT") (class "Default")
      (node (ref "ASV1") (pin "2") (pinfunction "2_2") (pintype "bidirectional"))
      (node (ref "OPTO1") (pin "4") (pinfunction "4_4") (pintype "bidirectional"))
      (node (ref "R35") (pin "1") (pinfunction "1_1") (pintype "passive"))
    )
    (net (code "21") (name "ASV1_PWM") (class "Default")
      (node (ref "R34") (pin "1") (pinfunction "1_1") (pintype "passive"))
      (node (ref "STM32") (pin "66") (pinfunction "PC9_66") (pintype "bidirectional"))
    )
    (net (code "22") (name "ASV2_OUT") (class "Default")
      (node (ref "ASV2") (pin "2") (pinfunction "2_2") (pintype "bidirectional"))
      (node (ref "OPTO2") (pin "4") (pinfunction "4_4") (pintype "bidirectional"))
      (node (ref "R37") (pin "1") (pinfunction "1_1") (pintype "passive"))
    )
    (net (code "23") (name "ASV2_PWM") (class "Default")
      (node (ref "R36") (pin "1") (pinfunction "1_1") (pintype "passive"))
      (node (ref "STM32") (pin "65") (pinfunction "PC8_65") (pintype "bidirectional"))
    )
    (net (code "24") (name "ASV3_OUT") (class "Default")
      (node (ref "ASV3") (pin "2") (pinfunction "2_2") (pintype "bidirectional"))
      (node (ref "OPTO3") (pin "4") (pinfunction "4_4") (pintype "bidirectional"))
      (node (ref "R39") (pin "1") (pinfunction "1_1") (pintype "passive"))
    )
    (net (code "25") (name "ASV3_PWM") (class "Default")
      (node (ref "R38") (pin "1") (pinfunction "1_1") (pintype "passive"))
      (node (ref "STM32") (pin "64") (pinfunction "PC7_64") (pintype "bidirectional"))
    )
    (net (code "26") (name "ASV4_OUT") (class "Default")
      (node (ref "ASV4") (pin "2") (pinfunction "2_2") (pintype "bidirectional"))
      (node (ref "OPTO4") (pin "4") (pinfunction "4_4") (pintype "bidirectional"))
      (node (ref "R41") (pin "1") (pinfunction "1_1") (pintype "passive"))
    )
    (net (code "27") (name "ASV4_PWM") (class "Default")
      (node (ref "R40") (pin "1") (pinfunction "1_1") (pintype "passive"))
      (node (ref "STM32") (pin "63") (pinfunction "PC6_63") (pintype "bidirectional"))
    )
    (net (code "28") (name "ASV5_OUT") (class "Default")
      (node (ref "ASV5") (pin "2") (pinfunction "2_2") (pintype "bidirectional"))
      (node (ref "OPTO5") (pin "4") (pinfunction "4_4") (pintype "bidirectional"))
      (node (ref "R43") (pin "1") (pinfunction "1_1") (pintype "passive"))
    )
    (net (code "29") (name "ASV5_PWM") (class "Default")
      (node (ref "R42") (pin "1") (pinfunction "1_1") (pintype "passive"))
      (node (ref "STM32") (pin "22") (pinfunction "PA0-WKUP_22") (pintype "bidirectional"))
    )
    (net (code "30") (name "ASV6_OUT") (class "Default")
      (node (ref "ASV6") (pin "2") (pinfunction "2_2") (pintype "bidirectional"))
      (node (ref "OPTO6") (pin "4") (pinfunction "4_4") (pintype "bidirectional"))
      (node (ref "R46") (pin "1") (pinfunction "1_1") (pintype "passive"))
    )
    (net (code "31") (name "ASV6_PWM") (class "Default")
      (node (ref "R45") (pin "1") (pinfunction "1_1") (pintype "passive"))
      (node (ref "STM32") (pin "23") (pinfunction "PA1_23") (pintype "bidirectional"))
    )
    (net (code "32") (name "ASV7_OUT") (class "Default")
      (node (ref "ASV7") (pin "2") (pinfunction "2_2") (pintype "bidirectional"))
      (node (ref "OPTO7") (pin "4") (pinfunction "4_4") (pintype "bidirectional"))
      (node (ref "R49") (pin "1") (pinfunction "1_1") (pintype "passive"))
    )
    (net (code "33") (name "ASV7_PWM") (class "Default")
      (node (ref "R48") (pin "1") (pinfunction "1_1") (pintype "passive"))
      (node (ref "STM32") (pin "24") (pinfunction "PA2_24") (pintype "bidirectional"))
    )
    (net (code "34") (name "ASV8_OUT") (class "Default")
      (node (ref "ASV8") (pin "2") (pinfunction "2_2") (pintype "bidirectional"))
      (node (ref "OPTO8") (pin "4") (pinfunction "4_4") (pintype "bidirectional"))
      (node (ref "R51") (pin "1") (pinfunction "1_1") (pintype "passive"))
    )
    (net (code "35") (name "ASV8_PWM") (class "Default")
      (node (ref "R50") (pin "1") (pinfunction "1_1") (pintype "passive"))
      (node (ref "STM32") (pin "25") (pinfunction "PA3_25") (pintype "bidirectional"))
    )
    (net (code "36") (name "BOOT0") (class "Default")
      (node (ref "R4") (pin "2") (pinfunction "2_2") (pintype "passive"))
      (node (ref "SJ2") (pin "1") (pinfunction "1_1") (pintype "passive"))
      (node (ref "STM32") (pin "94") (pinfunction "BOOT0_94") (pintype "bidirectional"))
    )
    (net (code "37") (name "CANH") (class "Default")
      (node (ref "HMI") (pin "14") (pinfunction "14_14") (pintype "bidirectional"))
      (node (ref "SJ4") (pin "1") (pinfunction "1_1") (pintype "passive"))
      (node (ref "UCAN") (pin "7") (pinfunction "CANH_7") (pintype "bidirectional"))
    )
    (net (code "38") (name "CANL") (class "Default")
      (node (ref "HMI") (pin "16") (pinfunction "16_16") (pintype "bidirectional"))
      (node (ref "R77") (pin "2") (pinfunction "2_2") (pintype "passive"))
      (node (ref "UCAN") (pin "6") (pinfunction "CANL_6") (pintype "bidirectional"))
    )
    (net (code "39") (name "CAN_RX") (class "Default")
      (node (ref "STM32") (pin "81") (pinfunction "PD0_81") (pintype "bidirectional"))
      (node (ref "UCAN") (pin "4") (pinfunction "RXD_4") (pintype "bidirectional"))
    )
    (net (code "40") (name "CAN_TX") (class "Default")
      (node (ref "STM32") (pin "82") (pinfunction "PD1_82") (pintype "bidirectional"))
      (node (ref "UCAN") (pin "1") (pinfunction "TXD_1") (pintype "bidirectional"))
    )
    (net (code "41") (name "DEBUG_CTS") (class "Default")
      (node (ref "STM32") (pin "70") (pinfunction "PA11_70") (pintype "bidirectional"))
      (node (ref "UART") (pin "4") (pinfunction "4_4") (pintype "passive"))
    )
    (net (code "42") (name "DEBUG_RTS") (class "Default")
      (node (ref "STM32") (pin "71") (pinfunction "PA12_71") (pintype "bidirectional"))
      (node (ref "UART") (pin "3") (pinfunction "3_3") (pintype "passive"))
    )
    (net (code "43") (name "DEBUG_RX") (class "Default")
      (node (ref "STM32") (pin "69") (pinfunction "PA10_69") (pintype "bidirectional"))
      (node (ref "UART") (pin "1") (pinfunction "1_1") (pintype "passive"))
    )
    (net (code "44") (name "DEBUG_TX") (class "Default")
      (node (ref "STM32") (pin "68") (pinfunction "PA9_68") (pintype "bidirectional"))
      (node (ref "UART") (pin "2") (pinfunction "2_2") (pintype "passive"))
    )
    (net (code "45") (name "DSV_TXRX") (class "Default")
      (node (ref "DSV1") (pin "3") (pinfunction "3_3") (pintype "bidirectional"))
      (node (ref "DSV2") (pin "3") (pinfunction "3_3") (pintype "bidirectional"))
      (node (ref "DSV3") (pin "3") (pinfunction "3_3") (pintype "bidirectional"))
      (node (ref "STM32") (pin "46") (pinfunction "PB10_46") (pintype "bidirectional"))
    )
    (net (code "46") (name "ENC1_A") (class "Default")
      (node (ref "ENC1") (pin "2") (pinfunction "2_2") (pintype "bidirectional"))
      (node (ref "R64") (pin "1") (pinfunction "1_1") (pintype "passive"))
      (node (ref "STM32") (pin "90") (pinfunction "PB4_90") (pintype "bidirectional"))
    )
    (net (code "47") (name "ENC1_B") (class "Default")
      (node (ref "ENC1") (pin "3") (pinfunction "3_3") (pintype "bidirectional"))
      (node (ref "R65") (pin "1") (pinfunction "1_1") (pintype "passive"))
      (node (ref "STM32") (pin "91") (pinfunction "PB5_91") (pintype "bidirectional"))
    )
    (net (code "48") (name "ENC2_A") (class "Default")
      (node (ref "ENC2") (pin "2") (pinfunction "2_2") (pintype "bidirectional"))
      (node (ref "R66") (pin "1") (pinfunction "1_1") (pintype "passive"))
      (node (ref "STM32") (pin "92") (pinfunction "PB6_92") (pintype "bidirectional"))
    )
    (net (code "49") (name "ENC2_B") (class "Default")
      (node (ref "ENC2") (pin "3") (pinfunction "3_3") (pintype "bidirectional"))
      (node (ref "R67") (pin "1") (pinfunction "1_1") (pintype "passive"))
      (node (ref "STM32") (pin "93") (pinfunction "PB7_93") (pintype "bidirectional"))
    )
    (net (code "50") (name "END_1") (class "Default")
      (node (ref "END1") (pin "4") (pinfunction "4_4") (pintype "bidirectional"))
      (node (ref "STM32") (pin "15") (pinfunction "PC0_15") (pintype "bidirectional"))
    )
    (net (code "51") (name "END_2") (class "Default")
      (node (ref "END2") (pin "4") (pinfunction "4_4") (pintype "bidirectional"))
      (node (ref "STM32") (pin "16") (pinfunction "PC1_16") (pintype "bidirectional"))
    )
    (net (code "52") (name "END_3") (class "Default")
      (node (ref "END3") (pin "4") (pinfunction "4_4") (pintype "bidirectional"))
      (node (ref "STM32") (pin "36") (pinfunction "PB2_36") (pintype "bidirectional"))
    )
    (net (code "53") (name "END_4") (class "Default")
      (node (ref "END4") (pin "4") (pinfunction "4_4") (pintype "bidirectional"))
      (node (ref "STM32") (pin "47") (pinfunction "PB11_47") (pintype "bidirectional"))
    )
    (net (code "54") (name "END_5") (class "Default")
      (node (ref "END5") (pin "4") (pinfunction "4_4") (pintype "bidirectional"))
      (node (ref "STM32") (pin "77") (pinfunction "PA15_77") (pintype "bidirectional"))
    )
    (net (code "55") (name "END_6") (class "Default")
      (node (ref "END6") (pin "4") (pinfunction "4_4") (pintype "bidirectional"))
      (node (ref "STM32") (pin "78") (pinfunction "PC10_78") (pintype "bidirectional"))
    )
    (net (code "56") (name "END_7") (class "Default")
      (node (ref "END7") (pin "4") (pinfunction "4_4") (pintype "bidirectional"))
      (node (ref "STM32") (pin "79") (pinfunction "PC11_79") (pintype "bidirectional"))
    )
    (net (code "57") (name "END_8") (class "Default")
      (node (ref "END8") (pin "4") (pinfunction "4_4") (pintype "bidirectional"))
      (node (ref "STM32") (pin "80") (pinfunction "PC12_80") (pintype "bidirectional"))
    )
    (net (code "58") (name "GND") (class "Default")
      (node (ref "ASV1") (pin "3") (pinfunction "3_3") (pintype "bidirectional"))
      (node (ref "ASV2") (pin "3") (pinfunction "3_3") (pintype "bidirectional"))
      (node (ref "ASV3") (pin "3") (pinfunction "3_3") (pintype "bidirectional"))
      (node (ref "ASV4") (pin "3") (pinfunction "3_3") (pintype "bidirectional"))
      (node (ref "ASV5") (pin "3") (pinfunction "3_3") (pintype "bidirectional"))
      (node (ref "ASV6") (pin "3") (pinfunction "3_3") (pintype "bidirectional"))
      (node (ref "ASV7") (pin "3") (pinfunction "3_3") (pintype "bidirectional"))
      (node (ref "ASV8") (pin "3") (pinfunction "3_3") (pintype "bidirectional"))
      (node (ref "BAT1") (pin "2") (pinfunction "2_2") (pintype "bidirectional"))
      (node (ref "C1") (pin "2") (pinfunction "2_2") (pintype "passive"))
      (node (ref "C10") (pin "2") (pinfunction "2_2") (pintype "passive"))
      (node (ref "C11") (pin "2") (pinfunction "2_2") (pintype "passive"))
      (node (ref "C12") (pin "2") (pinfunction "2_2") (pintype "passive"))
      (node (ref "C13") (pin "2") (pinfunction "2_2") (pintype "passive"))
      (node (ref "C14") (pin "-") (pinfunction "-_-") (pintype "passive"))
      (node (ref "C15") (pin "2") (pinfunction "2_2") (pintype "passive"))
      (node (ref "C16") (pin "-") (pinfunction "-_-") (pintype "passive"))
      (node (ref "C17") (pin "2") (pinfunction "2_2") (pintype "passive"))
      (node (ref "C18") (pin "2") (pinfunction "2_2") (pintype "passive"))
      (node (ref "C19") (pin "-") (pinfunction "-_-") (pintype "passive"))
      (node (ref "C2") (pin "2") (pinfunction "2_2") (pintype "passive"))
      (node (ref "C20") (pin "2") (pinfunction "2_2") (pintype "passive"))
      (node (ref "C21") (pin "2") (pinfunction "2_2") (pintype "passive"))
      (node (ref "C22") (pin "-") (pinfunction "-_-") (pintype "passive"))
      (node (ref "C23") (pin "2") (pinfunction "2_2") (pintype "passive"))
      (node (ref "C24") (pin "2") (pinfunction "2_2") (pintype "passive"))
      (node (ref "C25") (pin "2") (pinfunction "2_2") (pintype "passive"))
      (node (ref "C26") (pin "2") (pinfunction "2_2") (pintype "passive"))
      (node (ref "C27") (pin "2") (pinfunction "2_2") (pintype "passive"))
      (node (ref "C28") (pin "2") (pinfunction "2_2") (pintype "passive"))
      (node (ref "C3") (pin "2") (pinfunction "2_2") (pintype "passive"))
      (node (ref "C30") (pin "2") (pinfunction "2_2") (pintype "passive"))
      (node (ref "C31") (pin "2") (pinfunction "2_2") (pintype "passive"))
      (node (ref "C33") (pin "2") (pinfunction "2_2") (pintype "passive"))
      (node (ref "C34") (pin "2") (pinfunction "2_2") (pintype "passive"))
      (node (ref "C36") (pin "2") (pinfunction "2_2") (pintype "passive"))
      (node (ref "C38") (pin "2") (pinfunction "2_2") (pintype "passive"))
      (node (ref "C39") (pin "2") (pinfunction "2_2") (pintype "passive"))
      (node (ref "C4") (pin "2") (pinfunction "2_2") (pintype "passive"))
      (node (ref "C40") (pin "2") (pinfunction "2_2") (pintype "passive"))
      (node (ref "C41") (pin "2") (pinfunction "2_2") (pintype "passive"))
      (node (ref "C42") (pin "2") (pinfunction "2_2") (pintype "passive"))
      (node (ref "C43") (pin "2") (pinfunction "2_2") (pintype "passive"))
      (node (ref "C44") (pin "2") (pinfunction "2_2") (pintype "passive"))
      (node (ref "C45") (pin "2") (pinfunction "2_2") (pintype "passive"))
      (node (ref "C46") (pin "2") (pinfunction "2_2") (pintype "passive"))
      (node (ref "C5") (pin "2") (pinfunction "2_2") (pintype "passive"))
      (node (ref "C6") (pin "2") (pinfunction "2_2") (pintype "passive"))
      (node (ref "C7") (pin "2") (pinfunction "2_2") (pintype "passive"))
      (node (ref "C8") (pin "2") (pinfunction "2_2") (pintype "passive"))
      (node (ref "C9") (pin "2") (pinfunction "2_2") (pintype "passive"))
      (node (ref "CEL1") (pin "1") (pinfunction "REF_1") (pintype "bidirectional"))
      (node (ref "CEL1") (pin "4") (pinfunction "V-_4") (pintype "bidirectional"))
      (node (ref "CEL2") (pin "1") (pinfunction "REF_1") (pintype "bidirectional"))
      (node (ref "CEL2") (pin "4") (pinfunction "V-_4") (pintype "bidirectional"))
      (node (ref "CEL3") (pin "1") (pinfunction "REF_1") (pintype "bidirectional"))
      (node (ref "CEL3") (pin "4") (pinfunction "V-_4") (pintype "bidirectional"))
      (node (ref "CEL4") (pin "1") (pinfunction "REF_1") (pintype "bidirectional"))
      (node (ref "CEL4") (pin "4") (pinfunction "V-_4") (pintype "bidirectional"))
      (node (ref "CX1") (pin "2") (pinfunction "P$3_2") (pintype "bidirectional"))
      (node (ref "CX1") (pin "4") (pinfunction "P$3_4") (pintype "bidirectional"))
      (node (ref "DSV1") (pin "1") (pinfunction "1_1") (pintype "bidirectional"))
      (node (ref "DSV2") (pin "1") (pinfunction "1_1") (pintype "bidirectional"))
      (node (ref "DSV3") (pin "2") (pinfunction "2_2") (pintype "bidirectional"))
      (node (ref "ENC1") (pin "4") (pinfunction "4_4") (pintype "bidirectional"))
      (node (ref "ENC2") (pin "4") (pinfunction "4_4") (pintype "bidirectional"))
      (node (ref "END1") (pin "3") (pinfunction "3_3") (pintype "bidirectional"))
      (node (ref "END2") (pin "3") (pinfunction "3_3") (pintype "bidirectional"))
      (node (ref "END3") (pin "3") (pinfunction "3_3") (pintype "bidirectional"))
      (node (ref "END4") (pin "3") (pinfunction "3_3") (pintype "bidirectional"))
      (node (ref "END5") (pin "3") (pinfunction "3_3") (pintype "bidirectional"))
      (node (ref "END6") (pin "3") (pinfunction "3_3") (pintype "bidirectional"))
      (node (ref "END7") (pin "3") (pinfunction "3_3") (pintype "bidirectional"))
      (node (ref "END8") (pin "3") (pinfunction "3_3") (pintype "bidirectional"))
      (node (ref "HMI") (pin "13") (pinfunction "13_13") (pintype "bidirectional"))
      (node (ref "HMI") (pin "15") (pinfunction "15_15") (pintype "bidirectional"))
      (node (ref "IBAT") (pin "2") (pinfunction "GND_2") (pintype "bidirectional"))
      (node (ref "IND1") (pin "3") (pinfunction "3_3") (pintype "bidirectional"))
      (node (ref "IND10") (pin "3") (pinfunction "3_3") (pintype "bidirectional"))
      (node (ref "IND2") (pin "3") (pinfunction "3_3") (pintype "bidirectional"))
      (node (ref "IND3") (pin "3") (pinfunction "3_3") (pintype "bidirectional"))
      (node (ref "IND4") (pin "3") (pinfunction "3_3") (pintype "bidirectional"))
      (node (ref "IND5") (pin "3") (pinfunction "3_3") (pintype "bidirectional"))
      (node (ref "IND6") (pin "3") (pinfunction "3_3") (pintype "bidirectional"))
      (node (ref "IND7") (pin "3") (pinfunction "3_3") (pintype "bidirectional"))
      (node (ref "IND8") (pin "3") (pinfunction "3_3") (pintype "bidirectional"))
      (node (ref "IND9") (pin "3") (pinfunction "3_3") (pintype "bidirectional"))
      (node (ref "IP1") (pin "2") (pinfunction "GND_2") (pintype "bidirectional"))
      (node (ref "IP2") (pin "2") (pinfunction "GND_2") (pintype "bidirectional"))
      (node (ref "IP3") (pin "2") (pinfunction "GND_2") (pintype "bidirectional"))
      (node (ref "OPA1") (pin "11") (pinfunction "V-_11") (pintype "power_in"))
      (node (ref "OPA2") (pin "11") (pinfunction "V-_11") (pintype "power_in"))
      (node (ref "OPTO1") (pin "2") (pinfunction "2_2") (pintype "bidirectional"))
      (node (ref "OPTO1") (pin "3") (pinfunction "3_3") (pintype "bidirectional"))
      (node (ref "OPTO10") (pin "3") (pinfunction "3_3") (pintype "bidirectional"))
      (node (ref "OPTO11") (pin "3") (pinfunction "3_3") (pintype "bidirectional"))
      (node (ref "OPTO12") (pin "3") (pinfunction "3_3") (pintype "bidirectional"))
      (node (ref "OPTO13") (pin "3") (pinfunction "3_3") (pintype "bidirectional"))
      (node (ref "OPTO14") (pin "3") (pinfunction "3_3") (pintype "bidirectional"))
      (node (ref "OPTO15") (pin "3") (pinfunction "3_3") (pintype "bidirectional"))
      (node (ref "OPTO16") (pin "3") (pinfunction "3_3") (pintype "bidirectional"))
      (node (ref "OPTO17") (pin "3") (pinfunction "3_3") (pintype "bidirectional"))
      (node (ref "OPTO18") (pin "3") (pinfunction "3_3") (pintype "bidirectional"))
      (node (ref "OPTO2") (pin "2") (pinfunction "2_2") (pintype "bidirectional"))
      (node (ref "OPTO2") (pin "3") (pinfunction "3_3") (pintype "bidirectional"))
      (node (ref "OPTO3") (pin "2") (pinfunction "2_2") (pintype "bidirectional"))
      (node (ref "OPTO3") (pin "3") (pinfunction "3_3") (pintype "bidirectional"))
      (node (ref "OPTO4") (pin "2") (pinfunction "2_2") (pintype "bidirectional"))
      (node (ref "OPTO4") (pin "3") (pinfunction "3_3") (pintype "bidirectional"))
      (node (ref "OPTO5") (pin "2") (pinfunction "2_2") (pintype "bidirectional"))
      (node (ref "OPTO5") (pin "3") (pinfunction "3_3") (pintype "bidirectional"))
      (node (ref "OPTO6") (pin "2") (pinfunction "2_2") (pintype "bidirectional"))
      (node (ref "OPTO6") (pin "3") (pinfunction "3_3") (pintype "bidirectional"))
      (node (ref "OPTO7") (pin "2") (pinfunction "2_2") (pintype "bidirectional"))
      (node (ref "OPTO7") (pin "3") (pinfunction "3_3") (pintype "bidirectional"))
      (node (ref "OPTO8") (pin "2") (pinfunction "2_2") (pintype "bidirectional"))
      (node (ref "OPTO8") (pin "3") (pinfunction "3_3") (pintype "bidirectional"))
      (node (ref "OPTO9") (pin "3") (pinfunction "3_3") (pintype "bidirectional"))
      (node (ref "Q1") (pin "2") (pinfunction "S_2") (pintype "passive"))
      (node (ref "Q2") (pin "2") (pinfunction "S_2") (pintype "passive"))
      (node (ref "Q3") (pin "2") (pinfunction "S_2") (pintype "passive"))
      (node (ref "R11") (pin "1") (pinfunction "1_1") (pintype "passive"))
      (node (ref "R12") (pin "1") (pinfunction "1_1") (pintype "passive"))
      (node (ref "R14") (pin "1") (pinfunction "1_1") (pintype "passive"))
      (node (ref "R15") (pin "1") (pinfunction "1_1") (pintype "passive"))
      (node (ref "R16") (pin "2") (pinfunction "2_2") (pintype "passive"))
      (node (ref "R17") (pin "2") (pinfunction "2_2") (pintype "passive"))
      (node (ref "R18") (pin "2") (pinfunction "2_2") (pintype "passive"))
      (node (ref "R19") (pin "2") (pinfunction "2_2") (pintype "passive"))
      (node (ref "R28") (pin "1") (pinfunction "1_1") (pintype "passive"))
      (node (ref "R32") (pin "1") (pinfunction "1_1") (pintype "passive"))
      (node (ref "R4") (pin "1") (pinfunction "1_1") (pintype "passive"))
      (node (ref "R47") (pin "1") (pinfunction "1_1") (pintype "passive"))
      (node (ref "R7") (pin "1") (pinfunction "1_1") (pintype "passive"))
      (node (ref "R78") (pin "1") (pinfunction "1_1") (pintype "passive"))
      (node (ref "R8") (pin "1") (pinfunction "1_1") (pintype "passive"))
      (node (ref "R80") (pin "2") (pinfunction "2_2") (pintype "passive"))
      (node (ref "R81") (pin "2") (pinfunction "2_2") (pintype "passive"))
      (node (ref "R9") (pin "1") (pinfunction "1_1") (pintype "passive"))
      (node (ref "RS485") (pin "2") (pinfunction "2_2") (pintype "passive"))
      (node (ref "RTC") (pin "3") (pinfunction "3_3") (pintype "passive"))
      (node (ref "STM32") (pin "10") (pinfunction "VSS_10") (pintype "bidirectional"))
      (node (ref "STM32") (pin "19") (pinfunction "VSSA_19") (pintype "bidirectional"))
      (node (ref "STM32") (pin "26") (pinfunction "VSS_26") (pintype "bidirectional"))
      (node (ref "STM32") (pin "49") (pinfunction "VSS_49") (pintype "bidirectional"))
      (node (ref "STM32") (pin "74") (pinfunction "VSS_74") (pintype "bidirectional"))
      (node (ref "STM32") (pin "99") (pinfunction "VSS_99") (pintype "bidirectional"))
      (node (ref "SWD") (pin "3") (pinfunction "3_3") (pintype "passive"))
      (node (ref "U12VL") (pin "2") (pinfunction "GND_2") (pintype "power_in"))
      (node (ref "U3V3L") (pin "2") (pinfunction "GND_2") (pintype "power_in"))
      (node (ref "U5VL") (pin "2") (pinfunction "GND_2") (pintype "power_in"))
      (node (ref "UART") (pin "5") (pinfunction "5_5") (pintype "passive"))
      (node (ref "UCAN") (pin "2") (pinfunction "GND_2") (pintype "bidirectional"))
      (node (ref "UMOT") (pin "1") (pinfunction "GND_1") (pintype "bidirectional"))
      (node (ref "UMOT") (pin "2") (pinfunction "GND_2") (pintype "bidirectional"))
      (node (ref "URS485") (pin "5") (pinfunction "GND_5") (pintype "bidirectional"))
      (node (ref "USB") (pin "5") (pinfunction "5_5") (pintype "passive"))
      (node (ref "UVP1") (pin "1") (pinfunction "GND_1") (pintype "power_in"))
      (node (ref "UVP1") (pin "7") (pinfunction "GND_7") (pintype "power_in"))
      (node (ref "UVP2") (pin "1") (pinfunction "GND_1") (pintype "power_in"))
      (node (ref "UVP2") (pin "7") (pinfunction "GND_7") (pintype "power_in"))
      (node (ref "UVP3") (pin "1") (pinfunction "GND_1") (pintype "power_in"))
      (node (ref "UVP3") (pin "7") (pinfunction "GND_7") (pintype "power_in"))
      (node (ref "VCC1") (pin "2") (pinfunction "2_2") (pintype "bidirectional"))
      (node (ref "VCC2") (pin "2") (pinfunction "2_2") (pintype "bidirectional"))
      (node (ref "VCC3") (pin "2") (pinfunction "2_2") (pintype "bidirectional"))
      (node (ref "VP1") (pin "2") (pinfunction "2_2") (pintype "bidirectional"))
      (node (ref "VP2") (pin "2") (pinfunction "2_2") (pintype "bidirectional"))
      (node (ref "VP3") (pin "2") (pinfunction "2_2") (pintype "bidirectional"))
      (node (ref "VREF") (pin "3") (pinfunction "GND_3") (pintype "power_in"))
    )
    (net (code "59") (name "HMI_IRQ_IN") (class "Default")
      (node (ref "HMI") (pin "10") (pinfunction "10_10") (pintype "bidirectional"))
      (node (ref "STM32") (pin "2") (pinfunction "PE3_2") (pintype "bidirectional"))
    )
    (net (code "60") (name "HMI_IRQ_OUT") (class "Default")
      (node (ref "HMI") (pin "12") (pinfunction "12_12") (pintype "bidirectional"))
      (node (ref "STM32") (pin "7") (pinfunction "PC13-ANTI_TAMP_7") (pintype "bidirectional"))
    )
    (net (code "61") (name "HMI_MISO") (class "Default")
      (node (ref "HMI") (pin "8") (pinfunction "8_8") (pintype "bidirectional"))
      (node (ref "STM32") (pin "4") (pinfunction "PE5_4") (pintype "bidirectional"))
    )
    (net (code "62") (name "HMI_MOSI") (class "Default")
      (node (ref "HMI") (pin "6") (pinfunction "6_6") (pintype "bidirectional"))
      (node (ref "STM32") (pin "5") (pinfunction "PE6_5") (pintype "bidirectional"))
    )
    (net (code "63") (name "HMI_SCK") (class "Default")
      (node (ref "HMI") (pin "4") (pinfunction "4_4") (pintype "bidirectional"))
      (node (ref "STM32") (pin "1") (pinfunction "PE2_1") (pintype "bidirectional"))
    )
    (net (code "64") (name "HMI_~{CSN}") (class "Default")
      (node (ref "HMI") (pin "2") (pinfunction "2_2") (pintype "bidirectional"))
      (node (ref "STM32") (pin "3") (pinfunction "PE4_3") (pintype "bidirectional"))
    )
    (net (code "65") (name "IBAT_SEN") (class "Default")
      (node (ref "IBAT") (pin "1") (pinfunction "OUT_1") (pintype "bidirectional"))
      (node (ref "OPA1") (pin "12") (pinfunction "+IN_12") (pintype "input"))
      (node (ref "R7") (pin "2") (pinfunction "2_2") (pintype "passive"))
    )
    (net (code "66") (name "IMOT1_SEN") (class "Default")
      (node (ref "OPA2") (pin "3") (pinfunction "+IN_3") (pintype "input"))
      (node (ref "UMOT") (pin "17") (pinfunction "ISENA_17") (pintype "bidirectional"))
    )
    (net (code "67") (name "IMOT2_SEN") (class "Default")
      (node (ref "OPA2") (pin "5") (pinfunction "+IN_5") (pintype "input"))
      (node (ref "UMOT") (pin "16") (pinfunction "ISENB_16") (pintype "bidirectional"))
    )
    (net (code "68") (name "IND_1") (class "Default")
      (node (ref "OPTO9") (pin "4") (pinfunction "4_4") (pintype "bidirectional"))
      (node (ref "R53") (pin "1") (pinfunction "1_1") (pintype "passive"))
      (node (ref "STM32") (pin "62") (pinfunction "PD15_62") (pintype "bidirectional"))
    )
    (net (code "69") (name "IND_2") (class "Default")
      (node (ref "OPTO10") (pin "4") (pinfunction "4_4") (pintype "bidirectional"))
      (node (ref "R55") (pin "1") (pinfunction "1_1") (pintype "passive"))
      (node (ref "STM32") (pin "61") (pinfunction "PD14_61") (pintype "bidirectional"))
    )
    (net (code "70") (name "IND_3") (class "Default")
      (node (ref "OPTO11") (pin "4") (pinfunction "4_4") (pintype "bidirectional"))
      (node (ref "R57") (pin "1") (pinfunction "1_1") (pintype "passive"))
      (node (ref "STM32") (pin "60") (pinfunction "PD13_60") (pintype "bidirectional"))
    )
    (net (code "71") (name "IND_4") (class "Default")
      (node (ref "OPTO12") (pin "4") (pinfunction "4_4") (pintype "bidirectional"))
      (node (ref "R59") (pin "1") (pinfunction "1_1") (pintype "passive"))
      (node (ref "STM32") (pin "59") (pinfunction "PD12_59") (pintype "bidirectional"))
    )
    (net (code "72") (name "IND_5") (class "Default")
      (node (ref "OPTO13") (pin "4") (pinfunction "4_4") (pintype "bidirectional"))
      (node (ref "R61") (pin "1") (pinfunction "1_1") (pintype "passive"))
      (node (ref "STM32") (pin "58") (pinfunction "PD11_58") (pintype "bidirectional"))
    )
    (net (code "73") (name "IND_6") (class "Default")
      (node (ref "OPTO14") (pin "4") (pinfunction "4_4") (pintype "bidirectional"))
      (node (ref "R63") (pin "1") (pinfunction "1_1") (pintype "passive"))
      (node (ref "STM32") (pin "57") (pinfunction "PD10_57") (pintype "bidirectional"))
    )
    (net (code "74") (name "IND_7") (class "Default")
      (node (ref "OPTO15") (pin "4") (pinfunction "4_4") (pintype "bidirectional"))
      (node (ref "R69") (pin "1") (pinfunction "1_1") (pintype "passive"))
      (node (ref "STM32") (pin "56") (pinfunction "PD9_56") (pintype "bidirectional"))
    )
    (net (code "75") (name "IND_8") (class "Default")
      (node (ref "OPTO16") (pin "4") (pinfunction "4_4") (pintype "bidirectional"))
      (node (ref "R71") (pin "1") (pinfunction "1_1") (pintype "passive"))
      (node (ref "STM32") (pin "55") (pinfunction "PD8_55") (pintype "bidirectional"))
    )
    (net (code "76") (name "IND_9") (class "Default")
      (node (ref "OPTO17") (pin "4") (pinfunction "4_4") (pintype "bidirectional"))
      (node (ref "R73") (pin "1") (pinfunction "1_1") (pintype "passive"))
      (node (ref "STM32") (pin "52") (pinfunction "PB13_52") (pintype "bidirectional"))
    )
    (net (code "77") (name "IND_10") (class "Default")
      (node (ref "OPTO18") (pin "4") (pinfunction "4_4") (pintype "bidirectional"))
      (node (ref "R75") (pin "1") (pinfunction "1_1") (pintype "passive"))
      (node (ref "STM32") (pin "51") (pinfunction "PB12_51") (pintype "bidirectional"))
    )
    (net (code "78") (name "IP1_SEN") (class "Default")
      (node (ref "IP1") (pin "1") (pinfunction "OUT_1") (pintype "bidirectional"))
      (node (ref "OPA1") (pin "3") (pinfunction "+IN_3") (pintype "input"))
      (node (ref "R9") (pin "2") (pinfunction "2_2") (pintype "passive"))
    )
    (net (code "79") (name "IP2_SEN") (class "Default")
      (node (ref "IP2") (pin "1") (pinfunction "OUT_1") (pintype "bidirectional"))
      (node (ref "OPA1") (pin "5") (pinfunction "+IN_5") (pintype "input"))
      (node (ref "R12") (pin "2") (pinfunction "2_2") (pintype "passive"))
    )
    (net (code "80") (name "IP3_SEN") (class "Default")
      (node (ref "IP3") (pin "1") (pinfunction "OUT_1") (pintype "bidirectional"))
      (node (ref "OPA1") (pin "10") (pinfunction "+IN_10") (pintype "input"))
      (node (ref "R15") (pin "2") (pinfunction "2_2") (pintype "passive"))
    )
    (net (code "81") (name "LEDB") (class "Default")
      (node (ref "R3") (pin "1") (pinfunction "1_1") (pintype "passive"))
      (node (ref "STM32") (pin "88") (pinfunction "PD7_88") (pintype "bidirectional"))
    )
    (net (code "82") (name "LEDG") (class "Default")
      (node (ref "R2") (pin "1") (pinfunction "1_1") (pintype "passive"))
      (node (ref "STM32") (pin "83") (pinfunction "PD2_83") (pintype "bidirectional"))
    )
    (net (code "83") (name "LEDR") (class "Default")
      (node (ref "R1") (pin "1") (pinfunction "1_1") (pintype "passive"))
      (node (ref "STM32") (pin "67") (pinfunction "PA8_67") (pintype "bidirectional"))
    )
    (net (code "84") (name "MOT1_DIR") (class "Default")
      (node (ref "STM32") (pin "44") (pinfunction "PE14_44") (pintype "bidirectional"))
      (node (ref "UMOT") (pin "19") (pinfunction "AIN2_19") (pintype "bidirectional"))
    )
    (net (code "85") (name "MOT1_PWM") (class "Default")
      (node (ref "STM32") (pin "43") (pinfunction "PE13_43") (pintype "bidirectional"))
      (node (ref "UMOT") (pin "20") (pinfunction "AIN1_20") (pintype "bidirectional"))
    )
    (net (code "86") (name "MOT2_DIR") (class "Default")
      (node (ref "STM32") (pin "39") (pinfunction "PE9_39") (pintype "bidirectional"))
      (node (ref "UMOT") (pin "22") (pinfunction "BIN2_22") (pintype "bidirectional"))
    )
    (net (code "87") (name "MOT2_PWM") (class "Default")
      (node (ref "STM32") (pin "41") (pinfunction "PE11_41") (pintype "bidirectional"))
      (node (ref "UMOT") (pin "21") (pinfunction "BIN1_21") (pintype "bidirectional"))
    )
    (net (code "88") (name "MOT_DECAY") (class "Default")
      (node (ref "P1") (pin "2") (pinfunction "S_2") (pintype "passive"))
      (node (ref "UMOT") (pin "18") (pinfunction "DECAY_18") (pintype "bidirectional"))
    )
    (net (code "89") (name "MOT_I0") (class "Default")
      (node (ref "STM32") (pin "38") (pinfunction "PE8_38") (pintype "bidirectional"))
      (node (ref "UMOT") (pin "23") (pinfunction "I0_23") (pintype "bidirectional"))
    )
    (net (code "90") (name "MOT_I1") (class "Default")
      (node (ref "STM32") (pin "37") (pinfunction "PE7_37") (pintype "bidirectional"))
      (node (ref "UMOT") (pin "24") (pinfunction "I1_24") (pintype "bidirectional"))
    )
    (net (code "91") (name "MOT_~{FAULT}") (class "Default")
      (node (ref "STM32") (pin "40") (pinfunction "PE10_40") (pintype "bidirectional"))
      (node (ref "UMOT") (pin "15") (pinfunction "~{FAULT}_15") (pintype "bidirectional"))
    )
    (net (code "92") (name "MOT_~{RESET}") (class "Default")
      (node (ref "STM32") (pin "42") (pinfunction "PE12_42") (pintype "bidirectional"))
      (node (ref "UMOT") (pin "13") (pinfunction "~{RESET}_13") (pintype "bidirectional"))
    )
    (net (code "93") (name "MOT_~{SLEEP}") (class "Default")
      (node (ref "STM32") (pin "45") (pinfunction "PE15_45") (pintype "bidirectional"))
      (node (ref "UMOT") (pin "14") (pinfunction "~{SLEEP}_14") (pintype "bidirectional"))
    )
    (net (code "94") (name "NRST") (class "Default")
      (node (ref "C1") (pin "1") (pinfunction "1_1") (pintype "passive"))
      (node (ref "SJ1") (pin "1") (pinfunction "1_1") (pintype "passive"))
      (node (ref "STM32") (pin "14") (pinfunction "NRST_14") (pintype "bidirectional"))
      (node (ref "SWD") (pin "5") (pinfunction "5_5") (pintype "passive"))
    )
    (net (code "95") (name "Net-(CEL1-IN+)") (class "Default")
      (node (ref "BAT2") (pin "2") (pinfunction "2_2") (pintype "bidirectional"))
      (node (ref "C29") (pin "2") (pinfunction "2_2") (pintype "passive"))
      (node (ref "C32") (pin "1") (pinfunction "1_1") (pintype "passive"))
      (node (ref "CEL1") (pin "3") (pinfunction "IN+_3") (pintype "bidirectional"))
      (node (ref "CEL2") (pin "2") (pinfunction "IN-_2") (pintype "bidirectional"))
      (node (ref "R20") (pin "1") (pinfunction "1_1") (pintype "passive"))
      (node (ref "R23") (pin "2") (pinfunction "2_2") (pintype "passive"))
    )
    (net (code "96") (name "Net-(CEL1-IN-)") (class "Default")
      (node (ref "BAT2") (pin "1") (pinfunction "1_1") (pintype "bidirectional"))
      (node (ref "C29") (pin "1") (pinfunction "1_1") (pintype "passive"))
      (node (ref "CEL1") (pin "2") (pinfunction "IN-_2") (pintype "bidirectional"))
      (node (ref "R20") (pin "2") (pinfunction "2_2") (pintype "passive"))
    )
    (net (code "97") (name "Net-(CEL2-IN+)") (class "Default")
      (node (ref "BAT2") (pin "3") (pinfunction "3_3") (pintype "bidirectional"))
      (node (ref "C32") (pin "2") (pinfunction "2_2") (pintype "passive"))
      (node (ref "C35") (pin "1") (pinfunction "1_1") (pintype "passive"))
      (node (ref "CEL2") (pin "3") (pinfunction "IN+_3") (pintype "bidirectional"))
      (node (ref "CEL3") (pin "2") (pinfunction "IN-_2") (pintype "bidirectional"))
      (node (ref "R23") (pin "1") (pinfunction "1_1") (pintype "passive"))
      (node (ref "R26") (pin "2") (pinfunction "2_2") (pintype "passive"))
    )
    (net (code "98") (name "Net-(CEL3-IN+)") (class "Default")
      (node (ref "BAT2") (pin "4") (pinfunction "4_4") (pintype "bidirectional"))
      (node (ref "C35") (pin "2") (pinfunction "2_2") (pintype "passive"))
      (node (ref "C37") (pin "1") (pinfunction "1_1") (pintype "passive"))
      (node (ref "CEL3") (pin "3") (pinfunction "IN+_3") (pintype "bidirectional"))
      (node (ref "CEL4") (pin "2") (pinfunction "IN-_2") (pintype "bidirectional"))
      (node (ref "R26") (pin "1") (pinfunction "1_1") (pintype "passive"))
      (node (ref "R29") (pin "2") (pinfunction "2_2") (pintype "passive"))
    )
    (net (code "99") (name "Net-(CEL4-IN+)") (class "Default")
      (node (ref "BAT2") (pin "5") (pinfunction "5_5") (pintype "bidirectional"))
      (node (ref "C37") (pin "2") (pinfunction "2_2") (pintype "passive"))
      (node (ref "CEL4") (pin "3") (pinfunction "IN+_3") (pintype "bidirectional"))
      (node (ref "R29") (pin "1") (pinfunction "1_1") (pintype "passive"))
    )
    (net (code "100") (name "Net-(IBAT-VIN+)") (class "Default")
      (node (ref "IBAT") (pin "3") (pinfunction "VIN+_3") (pintype "bidirectional"))
      (node (ref "R5") (pin "1") (pinfunction "1_1") (pintype "passive"))
      (node (ref "SWITCHS") (pin "3") (pinfunction "3_3") (pintype "bidirectional"))
    )
    (net (code "101") (name "Net-(IND1-Pad2)") (class "Default")
      (node (ref "IND1") (pin "2") (pinfunction "2_2") (pintype "bidirectional"))
      (node (ref "R52") (pin "1") (pinfunction "1_1") (pintype "passive"))
    )
    (net (code "102") (name "Net-(IND1-Pad4)") (class "Default")
      (node (ref "IND1") (pin "4") (pinfunction "4_4") (pintype "bidirectional"))
      (node (ref "OPTO9") (pin "2") (pinfunction "2_2") (pintype "bidirectional"))
    )
    (net (code "103") (name "Net-(IND2-Pad2)") (class "Default")
      (node (ref "IND2") (pin "2") (pinfunction "2_2") (pintype "bidirectional"))
      (node (ref "R54") (pin "1") (pinfunction "1_1") (pintype "passive"))
    )
    (net (code "104") (name "Net-(IND2-Pad4)") (class "Default")
      (node (ref "IND2") (pin "4") (pinfunction "4_4") (pintype "bidirectional"))
      (node (ref "OPTO10") (pin "2") (pinfunction "2_2") (pintype "bidirectional"))
    )
    (net (code "105") (name "Net-(IND3-Pad2)") (class "Default")
      (node (ref "IND3") (pin "2") (pinfunction "2_2") (pintype "bidirectional"))
      (node (ref "R56") (pin "1") (pinfunction "1_1") (pintype "passive"))
    )
    (net (code "106") (name "Net-(IND3-Pad4)") (class "Default")
      (node (ref "IND3") (pin "4") (pinfunction "4_4") (pintype "bidirectional"))
      (node (ref "OPTO11") (pin "2") (pinfunction "2_2") (pintype "bidirectional"))
    )
    (net (code "107") (name "Net-(IND4-Pad2)") (class "Default")
      (node (ref "IND4") (pin "2") (pinfunction "2_2") (pintype "bidirectional"))
      (node (ref "R58") (pin "1") (pinfunction "1_1") (pintype "passive"))
    )
    (net (code "108") (name "Net-(IND4-Pad4)") (class "Default")
      (node (ref "IND4") (pin "4") (pinfunction "4_4") (pintype "bidirectional"))
      (node (ref "OPTO12") (pin "2") (pinfunction "2_2") (pintype "bidirectional"))
    )
    (net (code "109") (name "Net-(IND5-Pad2)") (class "Default")
      (node (ref "IND5") (pin "2") (pinfunction "2_2") (pintype "bidirectional"))
      (node (ref "R60") (pin "1") (pinfunction "1_1") (pintype "passive"))
    )
    (net (code "110") (name "Net-(IND5-Pad4)") (class "Default")
      (node (ref "IND5") (pin "4") (pinfunction "4_4") (pintype "bidirectional"))
      (node (ref "OPTO13") (pin "2") (pinfunction "2_2") (pintype "bidirectional"))
    )
    (net (code "111") (name "Net-(IND6-Pad2)") (class "Default")
      (node (ref "IND6") (pin "2") (pinfunction "2_2") (pintype "bidirectional"))
      (node (ref "R62") (pin "1") (pinfunction "1_1") (pintype "passive"))
    )
    (net (code "112") (name "Net-(IND6-Pad4)") (class "Default")
      (node (ref "IND6") (pin "4") (pinfunction "4_4") (pintype "bidirectional"))
      (node (ref "OPTO14") (pin "2") (pinfunction "2_2") (pintype "bidirectional"))
    )
    (net (code "113") (name "Net-(IND7-Pad2)") (class "Default")
      (node (ref "IND7") (pin "2") (pinfunction "2_2") (pintype "bidirectional"))
      (node (ref "R68") (pin "1") (pinfunction "1_1") (pintype "passive"))
    )
    (net (code "114") (name "Net-(IND7-Pad4)") (class "Default")
      (node (ref "IND7") (pin "4") (pinfunction "4_4") (pintype "bidirectional"))
      (node (ref "OPTO15") (pin "2") (pinfunction "2_2") (pintype "bidirectional"))
    )
    (net (code "115") (name "Net-(IND8-Pad2)") (class "Default")
      (node (ref "IND8") (pin "2") (pinfunction "2_2") (pintype "bidirectional"))
      (node (ref "R70") (pin "1") (pinfunction "1_1") (pintype "passive"))
    )
    (net (code "116") (name "Net-(IND8-Pad4)") (class "Default")
      (node (ref "IND8") (pin "4") (pinfunction "4_4") (pintype "bidirectional"))
      (node (ref "OPTO16") (pin "2") (pinfunction "2_2") (pintype "bidirectional"))
    )
    (net (code "117") (name "Net-(IND9-Pad2)") (class "Default")
      (node (ref "IND9") (pin "2") (pinfunction "2_2") (pintype "bidirectional"))
      (node (ref "R72") (pin "1") (pinfunction "1_1") (pintype "passive"))
    )
    (net (code "118") (name "Net-(IND9-Pad4)") (class "Default")
      (node (ref "IND9") (pin "4") (pinfunction "4_4") (pintype "bidirectional"))
      (node (ref "OPTO17") (pin "2") (pinfunction "2_2") (pintype "bidirectional"))
    )
    (net (code "119") (name "Net-(IND10-Pad2)") (class "Default")
      (node (ref "IND10") (pin "2") (pinfunction "2_2") (pintype "bidirectional"))
      (node (ref "R74") (pin "1") (pinfunction "1_1") (pintype "passive"))
    )
    (net (code "120") (name "Net-(IND10-Pad4)") (class "Default")
      (node (ref "IND10") (pin "4") (pinfunction "4_4") (pintype "bidirectional"))
      (node (ref "OPTO18") (pin "2") (pinfunction "2_2") (pintype "bidirectional"))
    )
    (net (code "121") (name "Net-(IP1-VIN+)") (class "Default")
      (node (ref "C17") (pin "1") (pinfunction "1_1") (pintype "passive"))
      (node (ref "IP1") (pin "3") (pinfunction "VIN+_3") (pintype "bidirectional"))
      (node (ref "L1") (pin "2") (pinfunction "2_2") (pintype "passive"))
      (node (ref "R6") (pin "1") (pinfunction "1_1") (pintype "passive"))
    )
    (net (code "122") (name "Net-(IP2-VIN+)") (class "Default")
      (node (ref "C20") (pin "1") (pinfunction "1_1") (pintype "passive"))
      (node (ref "IP2") (pin "3") (pinfunction "VIN+_3") (pintype "bidirectional"))
      (node (ref "L2") (pin "2") (pinfunction "2_2") (pintype "passive"))
      (node (ref "R10") (pin "1") (pinfunction "1_1") (pintype "passive"))
    )
    (net (code "123") (name "Net-(IP3-VIN+)") (class "Default")
      (node (ref "C23") (pin "1") (pinfunction "1_1") (pintype "passive"))
      (node (ref "IP3") (pin "3") (pinfunction "VIN+_3") (pintype "bidirectional"))
      (node (ref "L3") (pin "2") (pinfunction "2_2") (pintype "passive"))
      (node (ref "R13") (pin "1") (pinfunction "1_1") (pintype "passive"))
    )
    (net (code "124") (name "Net-(LED1-CB)") (class "Default")
      (node (ref "LED1") (pin "2") (pinfunction "CB_2") (pintype "bidirectional"))
      (node (ref "R3") (pin "2") (pinfunction "2_2") (pintype "passive"))
    )
    (net (code "125") (name "Net-(LED1-CG)") (class "Default")
      (node (ref "LED1") (pin "3") (pinfunction "CG_3") (pintype "bidirectional"))
      (node (ref "R2") (pin "2") (pinfunction "2_2") (pintype "passive"))
    )
    (net (code "126") (name "Net-(LED1-CR)") (class "Default")
      (node (ref "LED1") (pin "4") (pinfunction "CR_4") (pintype "bidirectional"))
      (node (ref "R1") (pin "2") (pinfunction "2_2") (pintype "passive"))
    )
    (net (code "127") (name "Net-(LED4-PadC)") (class "Default")
      (node (ref "LED4") (pin "C") (pinfunction "C_C") (pintype "passive"))
      (node (ref "R16") (pin "1") (pinfunction "1_1") (pintype "passive"))
    )
    (net (code "128") (name "Net-(LED5-PadC)") (class "Default")
      (node (ref "LED5") (pin "C") (pinfunction "C_C") (pintype "passive"))
      (node (ref "R17") (pin "1") (pinfunction "1_1") (pintype "passive"))
    )
    (net (code "129") (name "Net-(LED6-PadC)") (class "Default")
      (node (ref "LED6") (pin "C") (pinfunction "C_C") (pintype "passive"))
      (node (ref "R18") (pin "1") (pinfunction "1_1") (pintype "passive"))
    )
    (net (code "130") (name "Net-(LED7-PadC)") (class "Default")
      (node (ref "LED7") (pin "C") (pinfunction "C_C") (pintype "passive"))
      (node (ref "R19") (pin "1") (pinfunction "1_1") (pintype "passive"))
    )
    (net (code "131") (name "Net-(LED8-PadC)") (class "Default")
      (node (ref "LED8") (pin "C") (pinfunction "C_C") (pintype "passive"))
      (node (ref "R80") (pin "1") (pinfunction "1_1") (pintype "passive"))
    )
    (net (code "132") (name "Net-(LED9-PadC)") (class "Default")
      (node (ref "LED9") (pin "C") (pinfunction "C_C") (pintype "passive"))
      (node (ref "R81") (pin "1") (pinfunction "1_1") (pintype "passive"))
    )
    (net (code "133") (name "Net-(MOT1-Pad1)") (class "Default")
      (node (ref "MOT1") (pin "1") (pinfunction "1_1") (pintype "bidirectional"))
      (node (ref "UMOT") (pin "3") (pinfunction "AOUT1_3") (pintype "bidirectional"))
      (node (ref "UMOT") (pin "4") (pinfunction "AOUT1_4") (pintype "bidirectional"))
    )
    (net (code "134") (name "Net-(MOT1-Pad2)") (class "Default")
      (node (ref "MOT1") (pin "2") (pinfunction "2_2") (pintype "bidirectional"))
      (node (ref "UMOT") (pin "5") (pinfunction "AOUT2_5") (pintype "bidirectional"))
      (node (ref "UMOT") (pin "6") (pinfunction "AOUT2_6") (pintype "bidirectional"))
    )
    (net (code "135") (name "Net-(MOT2-Pad1)") (class "Default")
      (node (ref "MOT2") (pin "1") (pinfunction "1_1") (pintype "bidirectional"))
      (node (ref "UMOT") (pin "10") (pinfunction "BOUT1_10") (pintype "bidirectional"))
      (node (ref "UMOT") (pin "9") (pinfunction "BOUT1_9") (pintype "bidirectional"))
    )
    (net (code "136") (name "Net-(MOT2-Pad2)") (class "Default")
      (node (ref "MOT2") (pin "2") (pinfunction "2_2") (pintype "bidirectional"))
      (node (ref "UMOT") (pin "7") (pinfunction "BOUT2_7") (pintype "bidirectional"))
      (node (ref "UMOT") (pin "8") (pinfunction "BOUT2_8") (pintype "bidirectional"))
    )
    (net (code "137") (name "Net-(OPA1A--IN)") (class "Default")
      (node (ref "OPA1") (pin "1") (pinfunction "OUT_1") (pintype "output"))
      (node (ref "OPA1") (pin "2") (pinfunction "-IN_2") (pintype "input"))
      (node (ref "R21") (pin "1") (pinfunction "1_1") (pintype "passive"))
    )
    (net (code "138") (name "Net-(OPA1B--IN)") (class "Default")
      (node (ref "OPA1") (pin "6") (pinfunction "-IN_6") (pintype "input"))
      (node (ref "OPA1") (pin "7") (pinfunction "OUT_7") (pintype "output"))
      (node (ref "R22") (pin "1") (pinfunction "1_1") (pintype "passive"))
    )
    (net (code "139") (name "Net-(OPA1C--IN)") (class "Default")
      (node (ref "OPA1") (pin "8") (pinfunction "OUT_8") (pintype "output"))
      (node (ref "OPA1") (pin "9") (pinfunction "-IN_9") (pintype "input"))
      (node (ref "R24") (pin "1") (pinfunction "1_1") (pintype "passive"))
    )
    (net (code "140") (name "Net-(OPA1D--IN)") (class "Default")
      (node (ref "OPA1") (pin "13") (pinfunction "-IN_13") (pintype "input"))
      (node (ref "OPA1") (pin "14") (pinfunction "OUT_14") (pintype "output"))
      (node (ref "R25") (pin "1") (pinfunction "1_1") (pintype "passive"))
    )
    (net (code "141") (name "Net-(OPA2A--IN)") (class "Default")
      (node (ref "OPA2") (pin "2") (pinfunction "-IN_2") (pintype "input"))
      (node (ref "R28") (pin "2") (pinfunction "2_2") (pintype "passive"))
      (node (ref "R30") (pin "1") (pinfunction "1_1") (pintype "passive"))
    )
    (net (code "142") (name "Net-(OPA2A-OUT)") (class "Default")
      (node (ref "OPA2") (pin "1") (pinfunction "OUT_1") (pintype "output"))
      (node (ref "R27") (pin "1") (pinfunction "1_1") (pintype "passive"))
      (node (ref "R30") (pin "2") (pinfunction "2_2") (pintype "passive"))
    )
    (net (code "143") (name "Net-(OPA2B--IN)") (class "Default")
      (node (ref "OPA2") (pin "6") (pinfunction "-IN_6") (pintype "input"))
      (node (ref "R32") (pin "2") (pinfunction "2_2") (pintype "passive"))
      (node (ref "R33") (pin "1") (pinfunction "1_1") (pintype "passive"))
    )
    (net (code "144") (name "Net-(OPA2B-OUT)") (class "Default")
      (node (ref "OPA2") (pin "7") (pinfunction "OUT_7") (pintype "output"))
      (node (ref "R31") (pin "1") (pinfunction "1_1") (pintype "passive"))
      (node (ref "R33") (pin "2") (pinfunction "2_2") (pintype "passive"))
    )
    (net (code "145") (name "Net-(OPTO1-Pad1)") (class "Default")
      (node (ref "OPTO1") (pin "1") (pinfunction "1_1") (pintype "bidirectional"))
      (node (ref "R34") (pin "2") (pinfunction "2_2") (pintype "passive"))
    )
    (net (code "146") (name "Net-(OPTO2-Pad1)") (class "Default")
      (node (ref "OPTO2") (pin "1") (pinfunction "1_1") (pintype "bidirectional"))
      (node (ref "R36") (pin "2") (pinfunction "2_2") (pintype "passive"))
    )
    (net (code "147") (name "Net-(OPTO3-Pad1)") (class "Default")
      (node (ref "OPTO3") (pin "1") (pinfunction "1_1") (pintype "bidirectional"))
      (node (ref "R38") (pin "2") (pinfunction "2_2") (pintype "passive"))
    )
    (net (code "148") (name "Net-(OPTO4-Pad1)") (class "Default")
      (node (ref "OPTO4") (pin "1") (pinfunction "1_1") (pintype "bidirectional"))
      (node (ref "R40") (pin "2") (pinfunction "2_2") (pintype "passive"))
    )
    (net (code "149") (name "Net-(OPTO5-Pad1)") (class "Default")
      (node (ref "OPTO5") (pin "1") (pinfunction "1_1") (pintype "bidirectional"))
      (node (ref "R42") (pin "2") (pinfunction "2_2") (pintype "passive"))
    )
    (net (code "150") (name "Net-(OPTO6-Pad1)") (class "Default")
      (node (ref "OPTO6") (pin "1") (pinfunction "1_1") (pintype "bidirectional"))
      (node (ref "R45") (pin "2") (pinfunction "2_2") (pintype "passive"))
    )
    (net (code "151") (name "Net-(OPTO7-Pad1)") (class "Default")
      (node (ref "OPTO7") (pin "1") (pinfunction "1_1") (pintype "bidirectional"))
      (node (ref "R48") (pin "2") (pinfunction "2_2") (pintype "passive"))
    )
    (net (code "152") (name "Net-(OPTO8-Pad1)") (class "Default")
      (node (ref "OPTO8") (pin "1") (pinfunction "1_1") (pintype "bidirectional"))
      (node (ref "R50") (pin "2") (pinfunction "2_2") (pintype "passive"))
    )
    (net (code "153") (name "Net-(OPTO9-Pad1)") (class "Default")
      (node (ref "OPTO9") (pin "1") (pinfunction "1_1") (pintype "bidirectional"))
      (node (ref "R52") (pin "2") (pinfunction "2_2") (pintype "passive"))
    )
    (net (code "154") (name "Net-(OPTO10-Pad1)") (class "Default")
      (node (ref "OPTO10") (pin "1") (pinfunction "1_1") (pintype "bidirectional"))
      (node (ref "R54") (pin "2") (pinfunction "2_2") (pintype "passive"))
    )
    (net (code "155") (name "Net-(OPTO11-Pad1)") (class "Default")
      (node (ref "OPTO11") (pin "1") (pinfunction "1_1") (pintype "bidirectional"))
      (node (ref "R56") (pin "2") (pinfunction "2_2") (pintype "passive"))
    )
    (net (code "156") (name "Net-(OPTO12-Pad1)") (class "Default")
      (node (ref "OPTO12") (pin "1") (pinfunction "1_1") (pintype "bidirectional"))
      (node (ref "R58") (pin "2") (pinfunction "2_2") (pintype "passive"))
    )
    (net (code "157") (name "Net-(OPTO13-Pad1)") (class "Default")
      (node (ref "OPTO13") (pin "1") (pinfunction "1_1") (pintype "bidirectional"))
      (node (ref "R60") (pin "2") (pinfunction "2_2") (pintype "passive"))
    )
    (net (code "158") (name "Net-(OPTO14-Pad1)") (class "Default")
      (node (ref "OPTO14") (pin "1") (pinfunction "1_1") (pintype "bidirectional"))
      (node (ref "R62") (pin "2") (pinfunction "2_2") (pintype "passive"))
    )
    (net (code "159") (name "Net-(OPTO15-Pad1)") (class "Default")
      (node (ref "OPTO15") (pin "1") (pinfunction "1_1") (pintype "bidirectional"))
      (node (ref "R68") (pin "2") (pinfunction "2_2") (pintype "passive"))
    )
    (net (code "160") (name "Net-(OPTO16-Pad1)") (class "Default")
      (node (ref "OPTO16") (pin "1") (pinfunction "1_1") (pintype "bidirectional"))
      (node (ref "R70") (pin "2") (pinfunction "2_2") (pintype "passive"))
    )
    (net (code "161") (name "Net-(OPTO17-Pad1)") (class "Default")
      (node (ref "OPTO17") (pin "1") (pinfunction "1_1") (pintype "bidirectional"))
      (node (ref "R72") (pin "2") (pinfunction "2_2") (pintype "passive"))
    )
    (net (code "162") (name "Net-(OPTO18-Pad1)") (class "Default")
      (node (ref "OPTO18") (pin "1") (pinfunction "1_1") (pintype "bidirectional"))
      (node (ref "R74") (pin "2") (pinfunction "2_2") (pintype "passive"))
    )
    (net (code "163") (name "Net-(P1-A)") (class "Default")
      (node (ref "P1") (pin "1") (pinfunction "A_1") (pintype "passive"))
      (node (ref "R44") (pin "1") (pinfunction "1_1") (pintype "passive"))
    )
    (net (code "164") (name "Net-(P1-E)") (class "Default")
      (node (ref "P1") (pin "3") (pinfunction "E_3") (pintype "passive"))
      (node (ref "R47") (pin "2") (pinfunction "2_2") (pintype "passive"))
    )
    (net (code "165") (name "Net-(Q1-D)") (class "Default")
      (node (ref "Q1") (pin "3") (pinfunction "D_3") (pintype "passive"))
      (node (ref "UVP1") (pin "3") (pinfunction "~{INHIBIT}_3") (pintype "input"))
    )
    (net (code "166") (name "Net-(Q2-D)") (class "Default")
      (node (ref "Q2") (pin "3") (pinfunction "D_3") (pintype "passive"))
      (node (ref "UVP2") (pin "3") (pinfunction "~{INHIBIT}_3") (pintype "input"))
    )
    (net (code "167") (name "Net-(Q3-D)") (class "Default")
      (node (ref "Q3") (pin "3") (pinfunction "D_3") (pintype "passive"))
      (node (ref "UVP3") (pin "3") (pinfunction "~{INHIBIT}_3") (pintype "input"))
    )
    (net (code "168") (name "Net-(R76-Pad2)") (class "Default")
      (node (ref "R76") (pin "2") (pinfunction "2_2") (pintype "passive"))
      (node (ref "SJ3") (pin "2") (pinfunction "2_2") (pintype "passive"))
    )
    (net (code "169") (name "Net-(R77-Pad1)") (class "Default")
      (node (ref "R77") (pin "1") (pinfunction "1_1") (pintype "passive"))
      (node (ref "SJ4") (pin "2") (pinfunction "2_2") (pintype "passive"))
    )
    (net (code "170") (name "Net-(R79-Pad2)") (class "Default")
      (node (ref "R79") (pin "2") (pinfunction "2_2") (pintype "passive"))
      (node (ref "SJ5") (pin "2") (pinfunction "2_2") (pintype "passive"))
    )
    (net (code "171") (name "Net-(UCAN-RS)") (class "Default")
      (node (ref "R78") (pin "2") (pinfunction "2_2") (pintype "passive"))
      (node (ref "UCAN") (pin "8") (pinfunction "RS_8") (pintype "bidirectional"))
    )
    (net (code "172") (name "Net-(UVP1-VO)") (class "Default")
      (node (ref "C16") (pin "+") (pinfunction "+_+") (pintype "passive"))
      (node (ref "L1") (pin "1") (pinfunction "1_1") (pintype "passive"))
      (node (ref "UVP1") (pin "5") (pinfunction "VO_SENSE_5") (pintype "input"))
      (node (ref "UVP1") (pin "6") (pinfunction "VO_6") (pintype "power_in"))
    )
    (net (code "173") (name "Net-(UVP1-VO_ADJ)") (class "Default")
      (node (ref "R8") (pin "2") (pinfunction "2_2") (pintype "passive"))
      (node (ref "UVP1") (pin "4") (pinfunction "VO_ADJ_4") (pintype "power_in"))
    )
    (net (code "174") (name "Net-(UVP2-VO)") (class "Default")
      (node (ref "C19") (pin "+") (pinfunction "+_+") (pintype "passive"))
      (node (ref "L2") (pin "1") (pinfunction "1_1") (pintype "passive"))
      (node (ref "UVP2") (pin "5") (pinfunction "VO_SENSE_5") (pintype "input"))
      (node (ref "UVP2") (pin "6") (pinfunction "VO_6") (pintype "power_in"))
    )
    (net (code "175") (name "Net-(UVP2-VO_ADJ)") (class "Default")
      (node (ref "R11") (pin "2") (pinfunction "2_2") (pintype "passive"))
      (node (ref "UVP2") (pin "4") (pinfunction "VO_ADJ_4") (pintype "power_in"))
    )
    (net (code "176") (name "Net-(UVP3-VO)") (class "Default")
      (node (ref "C22") (pin "+") (pinfunction "+_+") (pintype "passive"))
      (node (ref "L3") (pin "1") (pinfunction "1_1") (pintype "passive"))
      (node (ref "UVP3") (pin "5") (pinfunction "VO_SENSE_5") (pintype "input"))
      (node (ref "UVP3") (pin "6") (pinfunction "VO_6") (pintype "power_in"))
    )
    (net (code "177") (name "Net-(UVP3-VO_ADJ)") (class "Default")
      (node (ref "R14") (pin "2") (pinfunction "2_2") (pintype "passive"))
      (node (ref "UVP3") (pin "4") (pinfunction "VO_ADJ_4") (pintype "power_in"))
    )
    (net (code "178") (name "OSC_IN") (class "Default")
      (node (ref "C2") (pin "1") (pinfunction "1_1") (pintype "passive"))
      (node (ref "CX1") (pin "1") (pinfunction "P$1_1") (pintype "bidirectional"))
      (node (ref "STM32") (pin "12") (pinfunction "PH0-OSC_IN_12") (pintype "bidirectional"))
    )
    (net (code "179") (name "OSC_OUT") (class "Default")
      (node (ref "C3") (pin "1") (pinfunction "1_1") (pintype "passive"))
      (node (ref "CX1") (pin "3") (pinfunction "P$2_3") (pintype "bidirectional"))
      (node (ref "STM32") (pin "13") (pinfunction "PH1-OSC_OUT_13") (pintype "bidirectional"))
    )
    (net (code "180") (name "RS485_A") (class "Default")
      (node (ref "RS485") (pin "6") (pinfunction "6_6") (pintype "passive"))
      (node (ref "SJ3") (pin "1") (pinfunction "1_1") (pintype "passive"))
      (node (ref "URS485") (pin "9") (pinfunction "A_9") (pintype "bidirectional"))
    )
    (net (code "181") (name "RS485_B") (class "Default")
      (node (ref "R76") (pin "1") (pinfunction "1_1") (pintype "passive"))
      (node (ref "RS485") (pin "5") (pinfunction "5_5") (pintype "passive"))
      (node (ref "URS485") (pin "8") (pinfunction "B_8") (pintype "bidirectional"))
    )
    (net (code "182") (name "RS485_DE") (class "Default")
      (node (ref "STM32") (pin "85") (pinfunction "PD4_85") (pintype "bidirectional"))
      (node (ref "URS485") (pin "3") (pinfunction "DE_3") (pintype "bidirectional"))
    )
    (net (code "183") (name "RS485_RX") (class "Default")
      (node (ref "STM32") (pin "87") (pinfunction "PD6_87") (pintype "bidirectional"))
      (node (ref "URS485") (pin "1") (pinfunction "R_1") (pintype "bidirectional"))
    )
    (net (code "184") (name "RS485_TX") (class "Default")
      (node (ref "STM32") (pin "86") (pinfunction "PD5_86") (pintype "bidirectional"))
      (node (ref "URS485") (pin "4") (pinfunction "T_4") (pintype "bidirectional"))
    )
    (net (code "185") (name "RS485_Y") (class "Default")
      (node (ref "R79") (pin "1") (pinfunction "1_1") (pintype "passive"))
      (node (ref "RS485") (pin "3") (pinfunction "3_3") (pintype "passive"))
      (node (ref "URS485") (pin "6") (pinfunction "Y_6") (pintype "bidirectional"))
    )
    (net (code "186") (name "RS485_Z") (class "Default")
      (node (ref "RS485") (pin "4") (pinfunction "4_4") (pintype "passive"))
      (node (ref "SJ5") (pin "1") (pinfunction "1_1") (pintype "passive"))
      (node (ref "URS485") (pin "7") (pinfunction "Z_7") (pintype "bidirectional"))
    )
    (net (code "187") (name "RS485_~{RE}") (class "Default")
      (node (ref "STM32") (pin "84") (pinfunction "PD3_84") (pintype "bidirectional"))
      (node (ref "URS485") (pin "2") (pinfunction "~{RE}_2") (pintype "bidirectional"))
    )
    (net (code "188") (name "SW1") (class "Default")
      (node (ref "HMI") (pin "3") (pinfunction "3_3") (pintype "bidirectional"))
      (node (ref "STM32") (pin "8") (pinfunction "PC14-OSC32_IN_8") (pintype "bidirectional"))
    )
    (net (code "189") (name "SW2") (class "Default")
      (node (ref "HMI") (pin "5") (pinfunction "5_5") (pintype "bidirectional"))
      (node (ref "STM32") (pin "9") (pinfunction "PC15-OSC32_OUT_9") (pintype "bidirectional"))
    )
    (net (code "190") (name "SW3") (class "Default")
      (node (ref "HMI") (pin "7") (pinfunction "7_7") (pintype "bidirectional"))
      (node (ref "STM32") (pin "98") (pinfunction "PE1_98") (pintype "bidirectional"))
    )
    (net (code "191") (name "SW4") (class "Default")
      (node (ref "HMI") (pin "9") (pinfunction "9_9") (pintype "bidirectional"))
      (node (ref "SJ1") (pin "2") (pinfunction "2_2") (pintype "passive"))
    )
    (net (code "192") (name "SW5") (class "Default")
      (node (ref "HMI") (pin "11") (pinfunction "11_11") (pintype "bidirectional"))
      (node (ref "SJ2") (pin "2") (pinfunction "2_2") (pintype "passive"))
    )
    (net (code "193") (name "SWD_SWCLK") (class "Default")
      (node (ref "STM32") (pin "76") (pinfunction "PA14_76") (pintype "bidirectional"))
      (node (ref "SWD") (pin "2") (pinfunction "2_2") (pintype "passive"))
    )
    (net (code "194") (name "SWD_SWDIO") (class "Default")
      (node (ref "STM32") (pin "72") (pinfunction "PA13_72") (pintype "bidirectional"))
      (node (ref "SWD") (pin "4") (pinfunction "4_4") (pintype "passive"))
    )
    (net (code "195") (name "SWD_SWO") (class "Default")
      (node (ref "STM32") (pin "89") (pinfunction "PB3_89") (pintype "bidirectional"))
      (node (ref "SWD") (pin "6") (pinfunction "6_6") (pintype "passive"))
    )
    (net (code "196") (name "USB_DM") (class "Default")
      (node (ref "STM32") (pin "53") (pinfunction "PB14_53") (pintype "bidirectional"))
      (node (ref "USB") (pin "2") (pinfunction "2_2") (pintype "passive"))
    )
    (net (code "197") (name "USB_DP") (class "Default")
      (node (ref "STM32") (pin "54") (pinfunction "PB15_54") (pintype "bidirectional"))
      (node (ref "USB") (pin "3") (pinfunction "3_3") (pintype "passive"))
    )
    (net (code "198") (name "VBAT_RTC") (class "Default")
      (node (ref "C28") (pin "1") (pinfunction "1_1") (pintype "passive"))
      (node (ref "RTC") (pin "2") (pinfunction "2_2") (pintype "passive"))
      (node (ref "STM32") (pin "6") (pinfunction "VBAT_6") (pintype "bidirectional"))
    )
    (net (code "199") (name "VCAP1") (class "Default")
      (node (ref "C12") (pin "1") (pinfunction "1_1") (pintype "passive"))
      (node (ref "STM32") (pin "48") (pinfunction "VCAP1_48") (pintype "bidirectional"))
    )
    (net (code "200") (name "VCAP2") (class "Default")
      (node (ref "C13") (pin "1") (pinfunction "1_1") (pintype "passive"))
      (node (ref "STM32") (pin "73") (pinfunction "VCAP2_73") (pintype "bidirectional"))
    )
    (net (code "201") (name "VP1_~{EN}") (class "Default")
      (node (ref "Q1") (pin "1") (pinfunction "G_1") (pintype "passive"))
      (node (ref "R82") (pin "1") (pinfunction "1_1") (pintype "passive"))
      (node (ref "STM32") (pin "95") (pinfunction "PB8_95") (pintype "bidirectional"))
    )
    (net (code "202") (name "VP2_~{EN}") (class "Default")
      (node (ref "Q2") (pin "1") (pinfunction "G_1") (pintype "passive"))
      (node (ref "R83") (pin "1") (pinfunction "1_1") (pintype "passive"))
      (node (ref "STM32") (pin "96") (pinfunction "PB9_96") (pintype "bidirectional"))
    )
    (net (code "203") (name "VP3_~{EN}") (class "Default")
      (node (ref "Q3") (pin "1") (pinfunction "G_1") (pintype "passive"))
      (node (ref "R84") (pin "1") (pinfunction "1_1") (pintype "passive"))
      (node (ref "STM32") (pin "97") (pinfunction "PE0_97") (pintype "bidirectional"))
    )
    (net (code "204") (name "VPACK") (class "Default")
      (node (ref "BAT1") (pin "1") (pinfunction "1_1") (pintype "bidirectional"))
      (node (ref "SWITCHS") (pin "4") (pinfunction "4_4") (pintype "bidirectional"))
    )
    (net (code "205") (name "unconnected-(CEL1-G1-Pad8)") (class "Default")
      (node (ref "CEL1") (pin "8") (pinfunction "G1_8") (pintype "bidirectional"))
    )
    (net (code "206") (name "unconnected-(CEL1-G2-Pad5)") (class "Default")
      (node (ref "CEL1") (pin "5") (pinfunction "G2_5") (pintype "bidirectional"))
    )
    (net (code "207") (name "unconnected-(CEL2-G1-Pad8)") (class "Default")
      (node (ref "CEL2") (pin "8") (pinfunction "G1_8") (pintype "bidirectional"))
    )
    (net (code "208") (name "unconnected-(CEL2-G2-Pad5)") (class "Default")
      (node (ref "CEL2") (pin "5") (pinfunction "G2_5") (pintype "bidirectional"))
    )
    (net (code "209") (name "unconnected-(CEL3-G1-Pad8)") (class "Default")
      (node (ref "CEL3") (pin "8") (pinfunction "G1_8") (pintype "bidirectional"))
    )
    (net (code "210") (name "unconnected-(CEL3-G2-Pad5)") (class "Default")
      (node (ref "CEL3") (pin "5") (pinfunction "G2_5") (pintype "bidirectional"))
    )
    (net (code "211") (name "unconnected-(CEL4-G1-Pad8)") (class "Default")
      (node (ref "CEL4") (pin "8") (pinfunction "G1_8") (pintype "bidirectional"))
    )
    (net (code "212") (name "unconnected-(CEL4-G2-Pad5)") (class "Default")
      (node (ref "CEL4") (pin "5") (pinfunction "G2_5") (pintype "bidirectional"))
    )
    (net (code "213") (name "unconnected-(END1-Pad2)") (class "Default")
      (node (ref "END1") (pin "2") (pinfunction "2_2") (pintype "bidirectional"))
    )
    (net (code "214") (name "unconnected-(END2-Pad2)") (class "Default")
      (node (ref "END2") (pin "2") (pinfunction "2_2") (pintype "bidirectional"))
    )
    (net (code "215") (name "unconnected-(END3-Pad2)") (class "Default")
      (node (ref "END3") (pin "2") (pinfunction "2_2") (pintype "bidirectional"))
    )
    (net (code "216") (name "unconnected-(END4-Pad2)") (class "Default")
      (node (ref "END4") (pin "2") (pinfunction "2_2") (pintype "bidirectional"))
    )
    (net (code "217") (name "unconnected-(END5-Pad2)") (class "Default")
      (node (ref "END5") (pin "2") (pinfunction "2_2") (pintype "bidirectional"))
    )
    (net (code "218") (name "unconnected-(END6-Pad2)") (class "Default")
      (node (ref "END6") (pin "2") (pinfunction "2_2") (pintype "bidirectional"))
    )
    (net (code "219") (name "unconnected-(END7-Pad2)") (class "Default")
      (node (ref "END7") (pin "2") (pinfunction "2_2") (pintype "bidirectional"))
    )
    (net (code "220") (name "unconnected-(END8-Pad2)") (class "Default")
      (node (ref "END8") (pin "2") (pinfunction "2_2") (pintype "bidirectional"))
    )
    (net (code "221") (name "unconnected-(RS485-Pad7)") (class "Default")
      (node (ref "RS485") (pin "7") (pinfunction "7_7") (pintype "passive"))
    )
    (net (code "222") (name "unconnected-(RS485-Pad8)") (class "Default")
      (node (ref "RS485") (pin "8") (pinfunction "8_8") (pintype "passive"))
    )
    (net (code "223") (name "unconnected-(UCAN-VREF-Pad5)") (class "Default")
      (node (ref "UCAN") (pin "5") (pinfunction "VREF_5") (pintype "bidirectional"))
    )
    (net (code "224") (name "unconnected-(USB-Pad1)") (class "Default")
      (node (ref "USB") (pin "1") (pinfunction "1_1") (pintype "passive"))
    )
    (net (code "225") (name "unconnected-(USB-Pad4)") (class "Default")
      (node (ref "USB") (pin "4") (pinfunction "4_4") (pintype "passive"))
    )
  )
)
